# octanis_v1.net
KiCad netlist of a schematic drawn in EAGLE
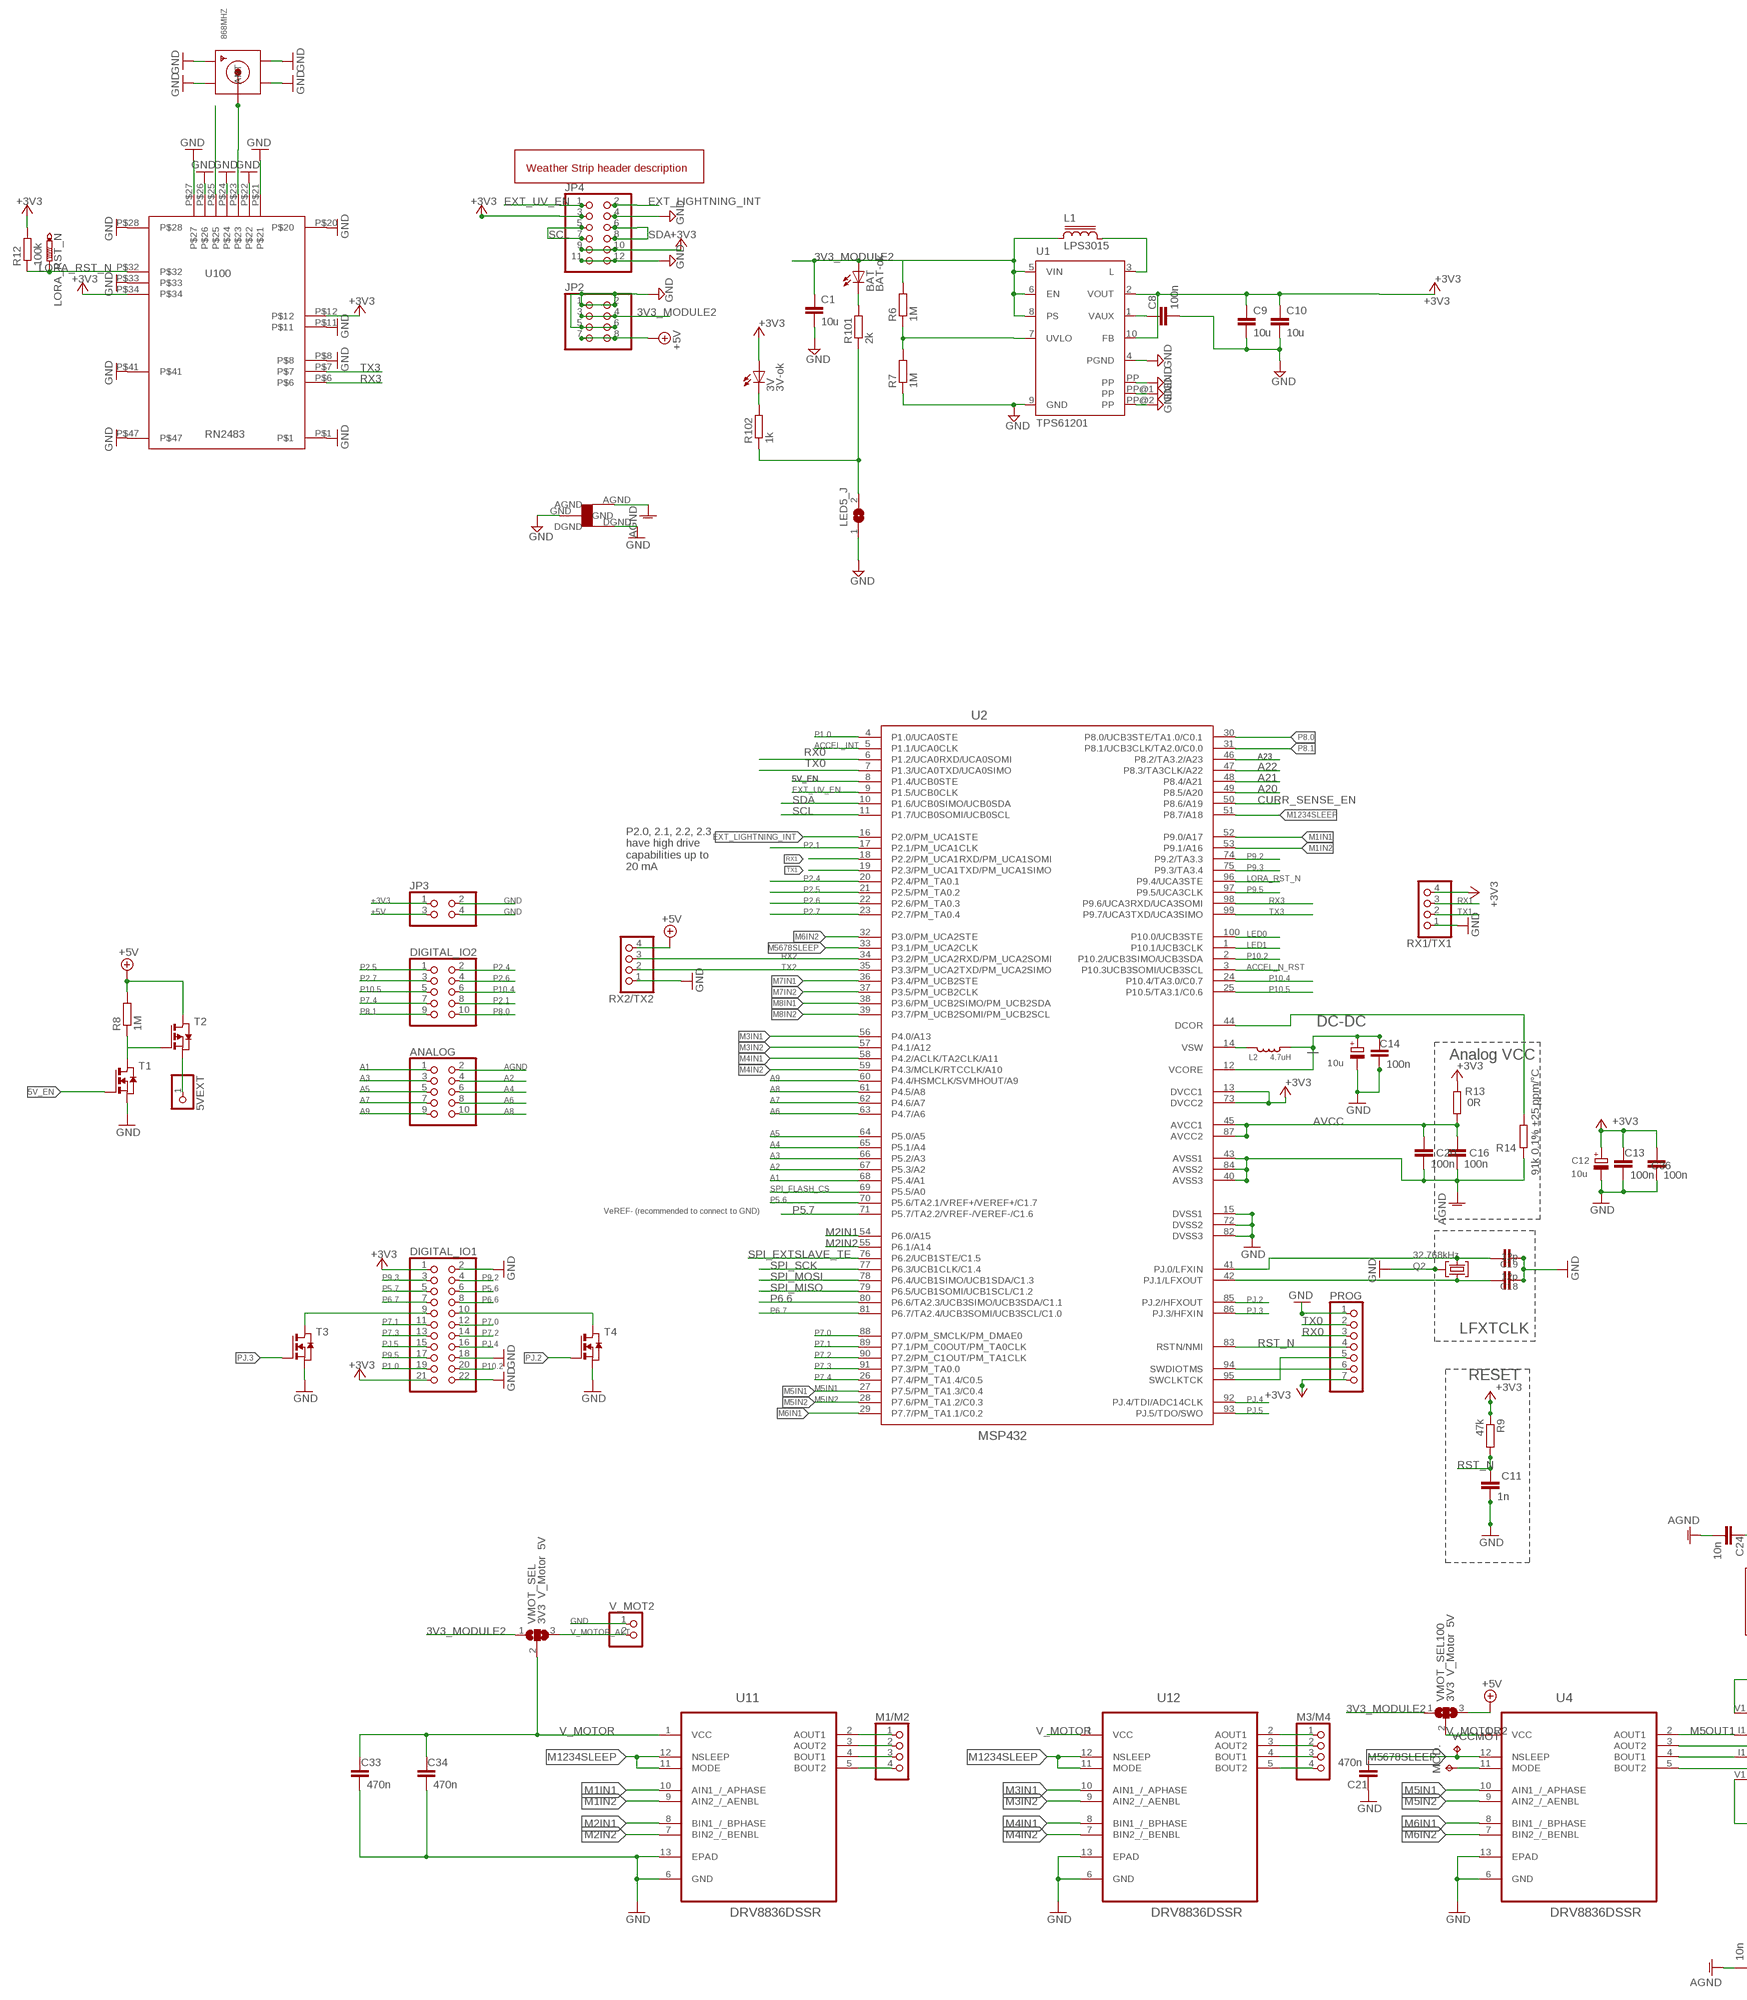
[diagram p0: schematic, sheet 1, part 1 of 2]
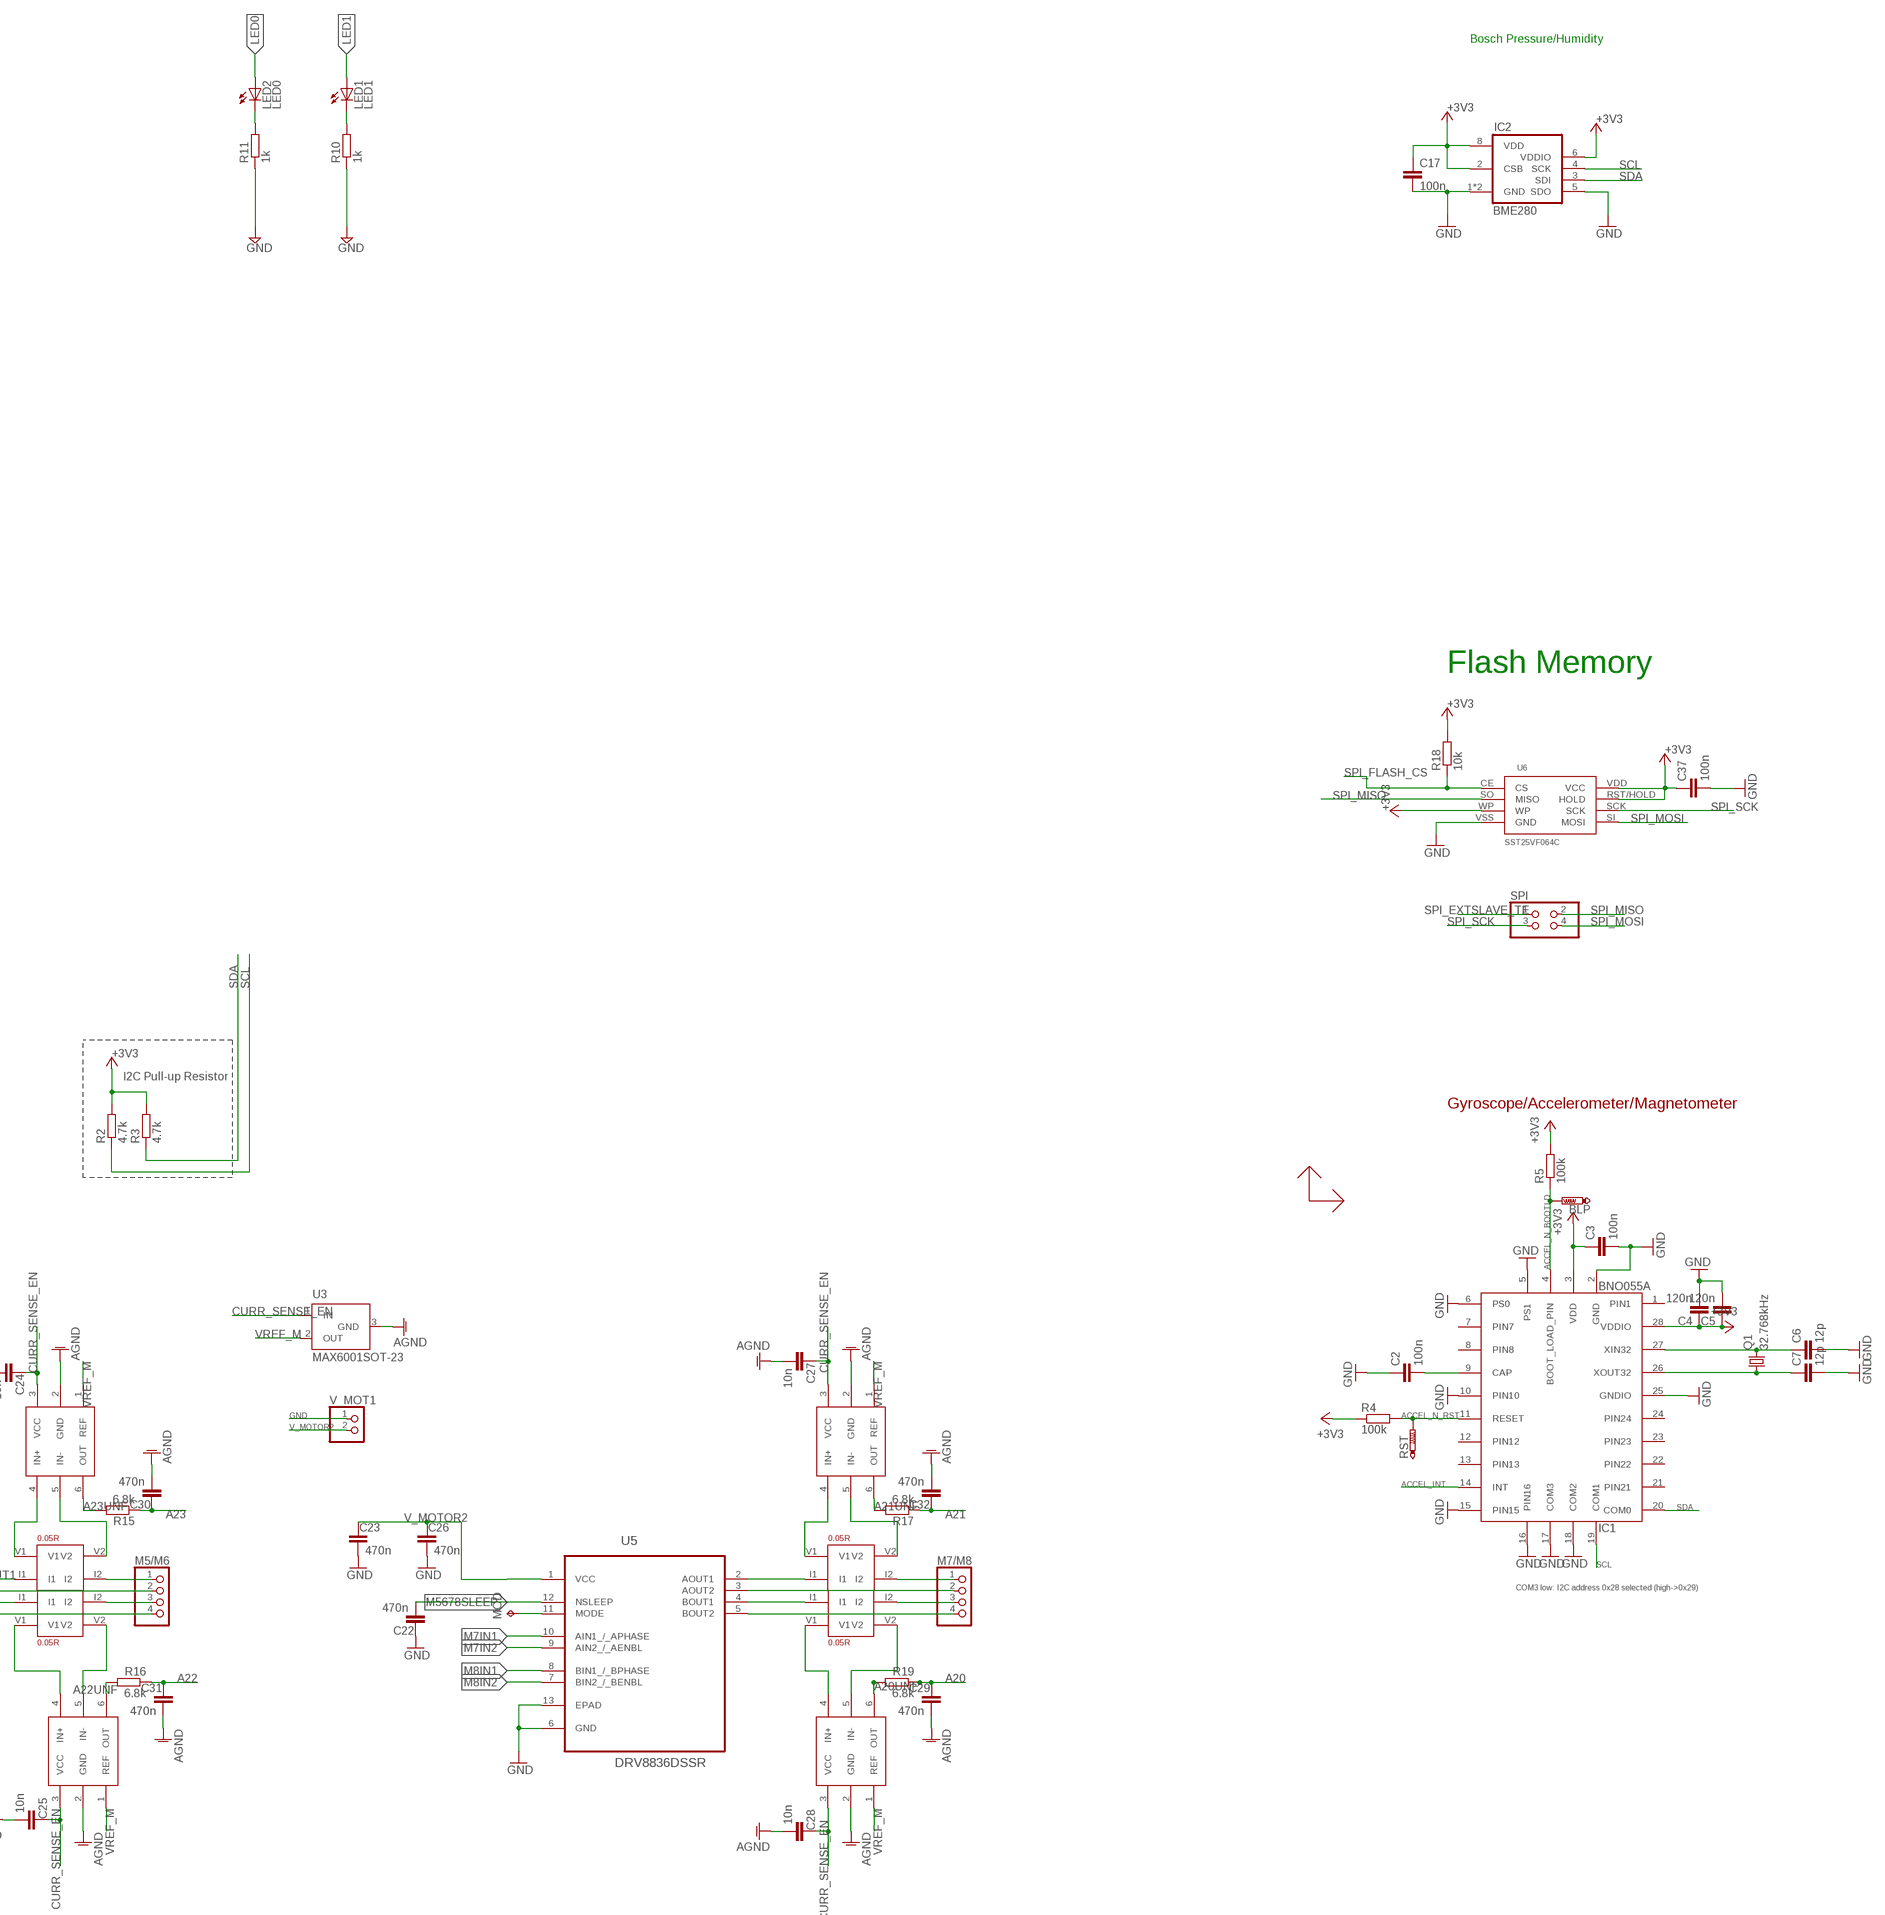
[diagram p1: schematic, sheet 1, part 2 of 2]

(export (version "E")
  (design (tool "Eeschema 10.0.6"))
  (components
    (comp (ref "3V")
      (value "3V-ok")
      (footprint "eagle-import:CHIPLED_0603")
      (libsource (lib "eagle-import") (part "LEDCHIPLED_0603"))
    )
    (comp (ref "5VEXT")
      (value "PINHD-1X1")
      (footprint "eagle-import:1X01")
      (libsource (lib "eagle-import") (part "PINHD-1X1"))
    )
    (comp (ref "868MHZ")
      (value "SMACONNECTOR_EDGE")
      (footprint "eagle-import:SMA_EDGELAUNCH")
      (libsource (lib "eagle-import") (part "SMACONNECTOR_EDGE"))
    )
    (comp (ref "ANALOG")
      (value "PINHD-2X5")
      (footprint "eagle-import:2X05")
      (libsource (lib "eagle-import") (part "PINHD-2X5"))
    )
    (comp (ref "BAT")
      (value "BAT-ok")
      (footprint "eagle-import:CHIPLED_0603")
      (libsource (lib "eagle-import") (part "LEDCHIPLED_0603"))
    )
    (comp (ref "BLP")
      (value "PTR1B1,27")
      (footprint "eagle-import:B1,27")
      (libsource (lib "eagle-import") (part "PTR1B1,27"))
    )
    (comp (ref "C1")
      (value "10u")
      (footprint "eagle-import:C0805K")
      (libsource (lib "eagle-import") (part "C-EUC0805K"))
    )
    (comp (ref "C2")
      (value "100n")
      (footprint "eagle-import:C0603")
      (libsource (lib "eagle-import") (part "C-EUC0603"))
    )
    (comp (ref "C3")
      (value "100n")
      (footprint "eagle-import:C0603")
      (libsource (lib "eagle-import") (part "C-EUC0603"))
    )
    (comp (ref "C4")
      (value "120n")
      (footprint "eagle-import:C0603")
      (libsource (lib "eagle-import") (part "C-EUC0603"))
    )
    (comp (ref "C5")
      (value "120n")
      (footprint "eagle-import:C0603")
      (libsource (lib "eagle-import") (part "C-EUC0603"))
    )
    (comp (ref "C6")
      (value "12p")
      (footprint "eagle-import:C0603")
      (libsource (lib "eagle-import") (part "C-EUC0603"))
    )
    (comp (ref "C7")
      (value "12p")
      (footprint "eagle-import:C0603")
      (libsource (lib "eagle-import") (part "C-EUC0603"))
    )
    (comp (ref "C8")
      (value "100n")
      (footprint "eagle-import:C0603")
      (libsource (lib "eagle-import") (part "C-EUC0603"))
    )
    (comp (ref "C9")
      (value "10u")
      (footprint "eagle-import:C0805K")
      (libsource (lib "eagle-import") (part "C-EUC0805K"))
    )
    (comp (ref "C10")
      (value "10u")
      (footprint "eagle-import:C0805K")
      (libsource (lib "eagle-import") (part "C-EUC0805K"))
    )
    (comp (ref "C11")
      (value "1n")
      (footprint "eagle-import:C0603")
      (libsource (lib "eagle-import") (part "C-EUC0603"))
    )
    (comp (ref "C12")
      (value "10u")
      (footprint "eagle-import:A_3216-18R")
      (libsource (lib "eagle-import") (part "CPOL-EUA/3216-18R"))
    )
    (comp (ref "C13")
      (value "100n")
      (footprint "eagle-import:C0603")
      (libsource (lib "eagle-import") (part "C-EUC0603"))
    )
    (comp (ref "C14")
      (value "100n")
      (footprint "eagle-import:C0603")
      (libsource (lib "eagle-import") (part "C-EUC0603"))
    )
    (comp (ref "C15")
      (value "10u")
      (footprint "eagle-import:A_3216-18R")
      (libsource (lib "eagle-import") (part "CPOL-EUA/3216-18R"))
    )
    (comp (ref "C16")
      (value "100n")
      (footprint "eagle-import:C0402")
      (libsource (lib "eagle-import") (part "C-EUC0402"))
    )
    (comp (ref "C17")
      (value "100n")
      (footprint "eagle-import:C0603")
      (libsource (lib "eagle-import") (part "C-EUC0603"))
    )
    (comp (ref "C18")
      (value "12p")
      (footprint "eagle-import:C0402")
      (libsource (lib "eagle-import") (part "C-EUC0402"))
    )
    (comp (ref "C19")
      (value "12p")
      (footprint "eagle-import:C0402")
      (libsource (lib "eagle-import") (part "C-EUC0402"))
    )
    (comp (ref "C20")
      (value "100n")
      (footprint "eagle-import:C0402")
      (libsource (lib "eagle-import") (part "C-EUC0402"))
    )
    (comp (ref "C21")
      (value "470n")
      (footprint "eagle-import:C0603")
      (libsource (lib "eagle-import") (part "C-EUC0603"))
    )
    (comp (ref "C22")
      (value "470n")
      (footprint "eagle-import:C0603")
      (libsource (lib "eagle-import") (part "C-EUC0603"))
    )
    (comp (ref "C23")
      (value "470n")
      (footprint "eagle-import:C0603")
      (libsource (lib "eagle-import") (part "C-EUC0603"))
    )
    (comp (ref "C24")
      (value "10n")
      (footprint "eagle-import:C0603")
      (libsource (lib "eagle-import") (part "C-EUC0603"))
    )
    (comp (ref "C25")
      (value "10n")
      (footprint "eagle-import:C0603")
      (libsource (lib "eagle-import") (part "C-EUC0603"))
    )
    (comp (ref "C26")
      (value "470n")
      (footprint "eagle-import:C0603")
      (libsource (lib "eagle-import") (part "C-EUC0603"))
    )
    (comp (ref "C27")
      (value "10n")
      (footprint "eagle-import:C0603")
      (libsource (lib "eagle-import") (part "C-EUC0603"))
    )
    (comp (ref "C28")
      (value "10n")
      (footprint "eagle-import:C0603")
      (libsource (lib "eagle-import") (part "C-EUC0603"))
    )
    (comp (ref "C29")
      (value "470n")
      (footprint "eagle-import:C0603")
      (libsource (lib "eagle-import") (part "C-EUC0603"))
    )
    (comp (ref "C30")
      (value "470n")
      (footprint "eagle-import:C0603")
      (libsource (lib "eagle-import") (part "C-EUC0603"))
    )
    (comp (ref "C31")
      (value "470n")
      (footprint "eagle-import:C0603")
      (libsource (lib "eagle-import") (part "C-EUC0603"))
    )
    (comp (ref "C32")
      (value "470n")
      (footprint "eagle-import:C0603")
      (libsource (lib "eagle-import") (part "C-EUC0603"))
    )
    (comp (ref "C33")
      (value "470n")
      (footprint "eagle-import:C0603")
      (libsource (lib "eagle-import") (part "C-EUC0603"))
    )
    (comp (ref "C34")
      (value "470n")
      (footprint "eagle-import:C0603")
      (libsource (lib "eagle-import") (part "C-EUC0603"))
    )
    (comp (ref "C36")
      (value "100n")
      (footprint "eagle-import:C0603")
      (libsource (lib "eagle-import") (part "C-EUC0603"))
    )
    (comp (ref "C37")
      (value "100n")
      (footprint "eagle-import:C0603")
      (libsource (lib "eagle-import") (part "C-EUC0603"))
    )
    (comp (ref "DIGITAL_IO1")
      (value "PINHD-2X11")
      (footprint "eagle-import:2X11")
      (libsource (lib "eagle-import") (part "PINHD-2X11"))
    )
    (comp (ref "DIGITAL_IO2")
      (value "PINHD-2X5")
      (footprint "eagle-import:2X05")
      (libsource (lib "eagle-import") (part "PINHD-2X5"))
    )
    (comp (ref "IC1")
      (value "BNO055A")
      (footprint "eagle-import:BNO055")
      (libsource (lib "eagle-import") (part "BNO055A"))
    )
    (comp (ref "IC2")
      (value "BME280")
      (footprint "eagle-import:BME280")
      (libsource (lib "eagle-import") (part "BME280"))
    )
    (comp (ref "JP2")
      (value "PINHD-2X04_2.54")
      (footprint "eagle-import:2X04")
      (libsource (lib "eagle-import") (part "PINHD-2X04_2.54"))
    )
    (comp (ref "JP3")
      (value "PINHD-2X2")
      (footprint "eagle-import:2X02")
      (libsource (lib "eagle-import") (part "PINHD-2X2"))
    )
    (comp (ref "JP4")
      (value "PINHD-2X06_2.54-SMD")
      (footprint "eagle-import:2X06SMD")
      (libsource (lib "eagle-import") (part "PINHD-2X06_2.54-SMD"))
    )
    (comp (ref "L1")
      (value "LPS3015")
      (footprint "eagle-import:LPS3015")
      (libsource (lib "eagle-import") (part "LPS3015"))
    )
    (comp (ref "L2")
      (value "4.7uH")
      (footprint "eagle-import:0806")
      (libsource (lib "eagle-import") (part "LQM2MP_G0"))
    )
    (comp (ref "LED1")
      (value "LED1")
      (footprint "eagle-import:CHIPLED_0603")
      (libsource (lib "eagle-import") (part "LEDCHIPLED_0603"))
    )
    (comp (ref "LED2")
      (value "LED0")
      (footprint "eagle-import:CHIPLED_0603")
      (libsource (lib "eagle-import") (part "LEDCHIPLED_0603"))
    )
    (comp (ref "LED5_J")
      (value "SJ")
      (footprint "eagle-import:SJ")
      (libsource (lib "eagle-import") (part "SJ"))
    )
    (comp (ref "LORA_RST_N")
      (value "PTR1TP15R")
      (footprint "eagle-import:TP15R")
      (libsource (lib "eagle-import") (part "PTR1TP15R"))
    )
    (comp (ref "M1/M2")
      (value "PINHD-1X04_2.54-S")
      (footprint "eagle-import:1X04-S")
      (libsource (lib "eagle-import") (part "PINHD-1X04_2.54-S"))
    )
    (comp (ref "M3/M4")
      (value "PINHD-1X04_2.54-S")
      (footprint "eagle-import:1X04-S")
      (libsource (lib "eagle-import") (part "PINHD-1X04_2.54-S"))
    )
    (comp (ref "M5/M6")
      (value "PINHD-1X04_2.54-S")
      (footprint "eagle-import:1X04-S")
      (libsource (lib "eagle-import") (part "PINHD-1X04_2.54-S"))
    )
    (comp (ref "M7/M8")
      (value "PINHD-1X04_2.54-S")
      (footprint "eagle-import:1X04-S")
      (libsource (lib "eagle-import") (part "PINHD-1X04_2.54-S"))
    )
    (comp (ref "MOD")
      (value "TPTP06R")
      (footprint "eagle-import:TP06R")
      (libsource (lib "eagle-import") (part "TPTP06R"))
    )
    (comp (ref "MOD.")
      (value "TPTP06R")
      (footprint "eagle-import:TP06R")
      (libsource (lib "eagle-import") (part "TPTP06R"))
    )
    (comp (ref "PROG")
      (value "PINHD-1X72MM_SMD")
      (footprint "eagle-import:1X7SMD")
      (libsource (lib "eagle-import") (part "PINHD-1X72MM_SMD"))
    )
    (comp (ref "Q1")
      (value "32.768kHz")
      (footprint "eagle-import:FC-12M")
      (libsource (lib "eagle-import") (part "FC-12M"))
    )
    (comp (ref "Q2")
      (value "32.768kHz")
      (footprint "eagle-import:MS3V-T1R")
      (libsource (lib "eagle-import") (part "MS3V-T1R"))
    )
    (comp (ref "R2")
      (value "4.7k")
      (footprint "eagle-import:R0603")
      (libsource (lib "eagle-import") (part "R-EU_R0603"))
    )
    (comp (ref "R3")
      (value "4.7k")
      (footprint "eagle-import:R0603")
      (libsource (lib "eagle-import") (part "R-EU_R0603"))
    )
    (comp (ref "R4")
      (value "100k")
      (footprint "eagle-import:R0603")
      (libsource (lib "eagle-import") (part "R-EU_R0603"))
    )
    (comp (ref "R5")
      (value "100k")
      (footprint "eagle-import:R0603")
      (libsource (lib "eagle-import") (part "R-EU_R0603"))
    )
    (comp (ref "R6")
      (value "1M")
      (footprint "eagle-import:R0603")
      (libsource (lib "eagle-import") (part "R-EU_R0603"))
    )
    (comp (ref "R7")
      (value "1M")
      (footprint "eagle-import:R0603")
      (libsource (lib "eagle-import") (part "R-EU_R0603"))
    )
    (comp (ref "R8")
      (value "1M")
      (footprint "eagle-import:R0603")
      (libsource (lib "eagle-import") (part "R-EU_R0603"))
    )
    (comp (ref "R9")
      (value "47k")
      (footprint "eagle-import:R0603")
      (libsource (lib "eagle-import") (part "R-EU_R0603"))
    )
    (comp (ref "R10")
      (value "1k")
      (footprint "eagle-import:R0603")
      (libsource (lib "eagle-import") (part "R-EU_R0603"))
    )
    (comp (ref "R11")
      (value "1k")
      (footprint "eagle-import:R0603")
      (libsource (lib "eagle-import") (part "R-EU_R0603"))
    )
    (comp (ref "R12")
      (value "100k")
      (footprint "eagle-import:R0603")
      (libsource (lib "eagle-import") (part "R-EU_R0603"))
    )
    (comp (ref "R13")
      (value "0R")
      (footprint "eagle-import:R0402")
      (libsource (lib "eagle-import") (part "R-EU_R0402"))
    )
    (comp (ref "R14")
      (value "91k 0.1% ±25 ppm/°C")
      (footprint "eagle-import:R0402")
      (libsource (lib "eagle-import") (part "R-EU_R0402"))
    )
    (comp (ref "R15")
      (value "6.8k")
      (footprint "eagle-import:R0603")
      (libsource (lib "eagle-import") (part "R-EU_R0603"))
    )
    (comp (ref "R16")
      (value "6.8k")
      (footprint "eagle-import:R0603")
      (libsource (lib "eagle-import") (part "R-EU_R0603"))
    )
    (comp (ref "R17")
      (value "6.8k")
      (footprint "eagle-import:R0603")
      (libsource (lib "eagle-import") (part "R-EU_R0603"))
    )
    (comp (ref "R18")
      (value "10k")
      (footprint "eagle-import:R0603")
      (libsource (lib "eagle-import") (part "R-EU_R0603"))
    )
    (comp (ref "R19")
      (value "6.8k")
      (footprint "eagle-import:R0603")
      (libsource (lib "eagle-import") (part "R-EU_R0603"))
    )
    (comp (ref "R101")
      (value "2k")
      (footprint "eagle-import:R0603")
      (libsource (lib "eagle-import") (part "R-EU_R0603"))
    )
    (comp (ref "R102")
      (value "1k")
      (footprint "eagle-import:R0603")
      (libsource (lib "eagle-import") (part "R-EU_R0603"))
    )
    (comp (ref "RS1")
      (value "0.05R")
      (footprint "eagle-import:4PADS_RESISTOR")
      (libsource (lib "eagle-import") (part "CURRENT_RESISTOR"))
    )
    (comp (ref "RS2")
      (value "0.05R")
      (footprint "eagle-import:4PADS_RESISTOR")
      (libsource (lib "eagle-import") (part "CURRENT_RESISTOR"))
    )
    (comp (ref "RS3")
      (value "0.05R")
      (footprint "eagle-import:4PADS_RESISTOR")
      (libsource (lib "eagle-import") (part "CURRENT_RESISTOR"))
    )
    (comp (ref "RS4")
      (value "0.05R")
      (footprint "eagle-import:4PADS_RESISTOR")
      (libsource (lib "eagle-import") (part "CURRENT_RESISTOR"))
    )
    (comp (ref "RST")
      (value "PTR1B1,27")
      (footprint "eagle-import:B1,27")
      (libsource (lib "eagle-import") (part "PTR1B1,27"))
    )
    (comp (ref "RX1/TX1")
      (value "PINHD-1X04_2.54-S")
      (footprint "eagle-import:1X04-S")
      (libsource (lib "eagle-import") (part "PINHD-1X04_2.54-S"))
    )
    (comp (ref "RX2/TX2")
      (value "PINHD-1X04_2.54-S")
      (footprint "eagle-import:1X04-S")
      (libsource (lib "eagle-import") (part "PINHD-1X04_2.54-S"))
    )
    (comp (ref "SPI")
      (value "PINHD-2X2")
      (footprint "eagle-import:2X02")
      (libsource (lib "eagle-import") (part "PINHD-2X2"))
    )
    (comp (ref "T1")
      (value "NMOSSOT23")
      (footprint "eagle-import:SOT-23")
      (libsource (lib "eagle-import") (part "NMOSSOT23"))
    )
    (comp (ref "T2")
      (value "PMOSSOT23")
      (footprint "eagle-import:SOT-23")
      (libsource (lib "eagle-import") (part "PMOSSOT23"))
    )
    (comp (ref "T3")
      (value "NMOSSOT23")
      (footprint "eagle-import:SOT-23")
      (libsource (lib "eagle-import") (part "NMOSSOT23"))
    )
    (comp (ref "T4")
      (value "NMOSSOT23")
      (footprint "eagle-import:SOT-23")
      (libsource (lib "eagle-import") (part "NMOSSOT23"))
    )
    (comp (ref "U$1")
      (value "WEATHER_STRIP_DOCU")
      (footprint "eagle-import:WEATHER_STRIP_DOCU")
      (libsource (lib "eagle-import") (part "WEATHER_STRIP_DOCU"))
    )
    (comp (ref "U$2")
      (value "STARGND")
      (footprint "eagle-import:STAR")
      (libsource (lib "eagle-import") (part "STARGND"))
    )
    (comp (ref "U$3")
      (value "BNO055_COORDINATES")
      (footprint "eagle-import:BNO055_COORDINATES")
      (libsource (lib "eagle-import") (part "BNO055_COORDINATES"))
    )
    (comp (ref "U1")
      (value "TPS61201")
      (footprint "eagle-import:S-PDSO-N10")
      (fields (field (name "MPN") "TPS61201DRCT"))
      (libsource (lib "eagle-import") (part "TPS61201"))
    )
    (comp (ref "U2")
      (value "MSP432")
      (footprint "eagle-import:PZ100")
      (libsource (lib "eagle-import") (part "MSP432"))
    )
    (comp (ref "U3")
      (value "MAX6001SOT-23")
      (footprint "eagle-import:MAX6001")
      (libsource (lib "eagle-import") (part "MAX6001SOT-23"))
    )
    (comp (ref "U4")
      (value "DRV8836DSSR")
      (footprint "eagle-import:SON50P200X300X80-13N")
      (fields (field (name "MPN") "DRV8836DSSR "))
      (libsource (lib "eagle-import") (part "DRV8836DSSR"))
    )
    (comp (ref "U5")
      (value "DRV8836DSSR")
      (footprint "eagle-import:SON50P200X300X80-13N")
      (fields (field (name "MPN") "DRV8836DSSR "))
      (libsource (lib "eagle-import") (part "DRV8836DSSR"))
    )
    (comp (ref "U6")
      (value "SST25VF064C")
      (footprint "eagle-import:SOIC_8-LEAD")
      (libsource (lib "eagle-import") (part "SST25VF064C"))
    )
    (comp (ref "U7")
      (value "INA210")
      (footprint "eagle-import:SC70-6")
      (libsource (lib "eagle-import") (part "INA213"))
    )
    (comp (ref "U8")
      (value "INA210")
      (footprint "eagle-import:SC70-6")
      (libsource (lib "eagle-import") (part "INA213"))
    )
    (comp (ref "U9")
      (value "INA210")
      (footprint "eagle-import:SC70-6")
      (libsource (lib "eagle-import") (part "INA213"))
    )
    (comp (ref "U10")
      (value "INA210")
      (footprint "eagle-import:SC70-6")
      (libsource (lib "eagle-import") (part "INA213"))
    )
    (comp (ref "U11")
      (value "DRV8836DSSR")
      (footprint "eagle-import:SON50P200X300X80-13N")
      (fields (field (name "MPN") "DRV8836DSSR "))
      (libsource (lib "eagle-import") (part "DRV8836DSSR"))
    )
    (comp (ref "U12")
      (value "DRV8836DSSR")
      (footprint "eagle-import:SON50P200X300X80-13N")
      (fields (field (name "MPN") "DRV8836DSSR "))
      (libsource (lib "eagle-import") (part "DRV8836DSSR"))
    )
    (comp (ref "U100")
      (value "RN2483")
      (footprint "eagle-import:RN2483")
      (libsource (lib "eagle-import") (part "RN2483"))
    )
    (comp (ref "VCCMOT")
      (value "TPTP06R")
      (footprint "eagle-import:TP06R")
      (libsource (lib "eagle-import") (part "TPTP06R"))
    )
    (comp (ref "VMOT_SEL")
      (value "3V3 V_Motor 5V")
      (footprint "eagle-import:SJ_2")
      (libsource (lib "eagle-import") (part "SJ2W"))
    )
    (comp (ref "VMOT_SEL100")
      (value "3V3 V_Motor 5V")
      (footprint "eagle-import:SJ_2")
      (libsource (lib "eagle-import") (part "SJ2W"))
    )
    (comp (ref "V_MOT1")
      (value "PINHD-1X02_2.54-S")
      (footprint "eagle-import:1X02-S")
      (libsource (lib "eagle-import") (part "PINHD-1X02_2.54-S"))
    )
    (comp (ref "V_MOT2")
      (value "PINHD-1X02_2.54-S")
      (footprint "eagle-import:1X02-S")
      (libsource (lib "eagle-import") (part "PINHD-1X02_2.54-S"))
    )
  )
  (nets
    (net (code "1") (name "+3V3") (class "Default")
      (node (ref "3V") (pin "A") (pinfunction "A_A") (pintype "passive"))
      (node (ref "C10") (pin "1") (pinfunction "1_1") (pintype "passive"))
      (node (ref "C12") (pin "+") (pinfunction "+_+") (pintype "passive"))
      (node (ref "C13") (pin "2") (pinfunction "2_2") (pintype "passive"))
      (node (ref "C17") (pin "1") (pinfunction "1_1") (pintype "passive"))
      (node (ref "C3") (pin "1") (pinfunction "1_1") (pintype "passive"))
      (node (ref "C36") (pin "2") (pinfunction "2_2") (pintype "passive"))
      (node (ref "C37") (pin "1") (pinfunction "1_1") (pintype "passive"))
      (node (ref "C4") (pin "1") (pinfunction "1_1") (pintype "passive"))
      (node (ref "C5") (pin "1") (pinfunction "1_1") (pintype "passive"))
      (node (ref "C9") (pin "1") (pinfunction "1_1") (pintype "passive"))
      (node (ref "DIGITAL_IO1") (pin "1") (pinfunction "1_1") (pintype "passive"))
      (node (ref "DIGITAL_IO1") (pin "21") (pinfunction "21_21") (pintype "passive"))
      (node (ref "IC1") (pin "28") (pinfunction "VDDIO_28") (pintype "bidirectional"))
      (node (ref "IC1") (pin "3") (pinfunction "VDD_3") (pintype "bidirectional"))
      (node (ref "IC2") (pin "2") (pinfunction "CSB_2") (pintype "input"))
      (node (ref "IC2") (pin "6") (pinfunction "VDDIO_6") (pintype "power_in"))
      (node (ref "IC2") (pin "8") (pinfunction "VDD_8") (pintype "power_in"))
      (node (ref "JP3") (pin "1") (pinfunction "1_1") (pintype "passive"))
      (node (ref "JP4") (pin "10") (pinfunction "10_10") (pintype "passive"))
      (node (ref "JP4") (pin "3") (pinfunction "3_3") (pintype "passive"))
      (node (ref "JP4") (pin "9") (pinfunction "9_9") (pintype "passive"))
      (node (ref "PROG") (pin "7") (pinfunction "7_7") (pintype "passive"))
      (node (ref "R12") (pin "2") (pinfunction "2_2") (pintype "passive"))
      (node (ref "R13") (pin "2") (pinfunction "2_2") (pintype "passive"))
      (node (ref "R18") (pin "2") (pinfunction "2_2") (pintype "passive"))
      (node (ref "R2") (pin "2") (pinfunction "2_2") (pintype "passive"))
      (node (ref "R3") (pin "2") (pinfunction "2_2") (pintype "passive"))
      (node (ref "R4") (pin "1") (pinfunction "1_1") (pintype "passive"))
      (node (ref "R5") (pin "2") (pinfunction "2_2") (pintype "passive"))
      (node (ref "R9") (pin "1") (pinfunction "1_1") (pintype "passive"))
      (node (ref "RX1/TX1") (pin "4") (pinfunction "4_4") (pintype "passive"))
      (node (ref "U1") (pin "10") (pinfunction "FB_10") (pintype "input"))
      (node (ref "U1") (pin "2") (pinfunction "VOUT_2") (pintype "passive"))
      (node (ref "U100") (pin "P$12") (pinfunction "P$12_P$12") (pintype "bidirectional"))
      (node (ref "U100") (pin "P$34") (pinfunction "P$34_P$34") (pintype "bidirectional"))
      (node (ref "U2") (pin "13") (pinfunction "DVCC1_13") (pintype "power_in"))
      (node (ref "U2") (pin "73") (pinfunction "DVCC2_73") (pintype "power_in"))
      (node (ref "U6") (pin "RST/HOLD") (pinfunction "HOLD_RST/HOLD") (pintype "bidirectional"))
      (node (ref "U6") (pin "VDD") (pinfunction "VCC_VDD") (pintype "bidirectional"))
      (node (ref "U6") (pin "WP") (pinfunction "WP_WP") (pintype "bidirectional"))
    )
    (net (code "2") (name "+5V") (class "Default")
      (node (ref "JP2") (pin "7") (pinfunction "7_7") (pintype "passive"))
      (node (ref "JP2") (pin "8") (pinfunction "8_8") (pintype "passive"))
      (node (ref "JP3") (pin "3") (pinfunction "3_3") (pintype "passive"))
      (node (ref "R8") (pin "2") (pinfunction "2_2") (pintype "passive"))
      (node (ref "RX2/TX2") (pin "4") (pinfunction "4_4") (pintype "passive"))
      (node (ref "T2") (pin "1") (pinfunction "D_1") (pintype "passive"))
      (node (ref "VMOT_SEL100") (pin "3") (pinfunction "3_3") (pintype "passive"))
    )
    (net (code "3") (name "/3V3_MODULE2") (class "Default")
      (node (ref "BAT") (pin "A") (pinfunction "A_A") (pintype "passive"))
      (node (ref "C1") (pin "1") (pinfunction "1_1") (pintype "passive"))
      (node (ref "JP2") (pin "3") (pinfunction "3_3") (pintype "passive"))
      (node (ref "JP2") (pin "4") (pinfunction "4_4") (pintype "passive"))
      (node (ref "L1") (pin "1") (pinfunction "1_1") (pintype "passive"))
      (node (ref "R6") (pin "2") (pinfunction "2_2") (pintype "passive"))
      (node (ref "U1") (pin "5") (pinfunction "VIN_5") (pintype "input"))
      (node (ref "U1") (pin "6") (pinfunction "EN_6") (pintype "input"))
      (node (ref "U1") (pin "8") (pinfunction "PS_8") (pintype "input"))
      (node (ref "VMOT_SEL") (pin "1") (pinfunction "1_1") (pintype "passive"))
      (node (ref "VMOT_SEL100") (pin "1") (pinfunction "1_1") (pintype "passive"))
    )
    (net (code "4") (name "/A1") (class "Default")
      (node (ref "ANALOG") (pin "1") (pinfunction "1_1") (pintype "passive"))
      (node (ref "U2") (pin "68") (pinfunction "P5.4/A1_68") (pintype "power_in"))
    )
    (net (code "5") (name "/A2") (class "Default")
      (node (ref "ANALOG") (pin "4") (pinfunction "4_4") (pintype "passive"))
      (node (ref "U2") (pin "67") (pinfunction "P5.3/A2_67") (pintype "power_in"))
    )
    (net (code "6") (name "/A3") (class "Default")
      (node (ref "ANALOG") (pin "3") (pinfunction "3_3") (pintype "passive"))
      (node (ref "U2") (pin "66") (pinfunction "P5.2/A3_66") (pintype "power_in"))
    )
    (net (code "7") (name "/A4") (class "Default")
      (node (ref "ANALOG") (pin "6") (pinfunction "6_6") (pintype "passive"))
      (node (ref "U2") (pin "65") (pinfunction "P5.1/A4_65") (pintype "power_in"))
    )
    (net (code "8") (name "/A5") (class "Default")
      (node (ref "ANALOG") (pin "5") (pinfunction "5_5") (pintype "passive"))
      (node (ref "U2") (pin "64") (pinfunction "P5.0/A5_64") (pintype "power_in"))
    )
    (net (code "9") (name "/A6") (class "Default")
      (node (ref "ANALOG") (pin "8") (pinfunction "8_8") (pintype "passive"))
      (node (ref "U2") (pin "63") (pinfunction "P4.7/A6_63") (pintype "power_in"))
    )
    (net (code "10") (name "/A7") (class "Default")
      (node (ref "ANALOG") (pin "7") (pinfunction "7_7") (pintype "passive"))
      (node (ref "U2") (pin "62") (pinfunction "P4.6/A7_62") (pintype "power_in"))
    )
    (net (code "11") (name "/A8") (class "Default")
      (node (ref "ANALOG") (pin "10") (pinfunction "10_10") (pintype "passive"))
      (node (ref "U2") (pin "61") (pinfunction "P4.5/A8_61") (pintype "power_in"))
    )
    (net (code "12") (name "/A9") (class "Default")
      (node (ref "ANALOG") (pin "9") (pinfunction "9_9") (pintype "passive"))
      (node (ref "U2") (pin "60") (pinfunction "P4.4/HSMCLK/SVMHOUT/A9_60") (pintype "power_in"))
    )
    (net (code "13") (name "/A20") (class "Default")
      (node (ref "C29") (pin "2") (pinfunction "2_2") (pintype "passive"))
      (node (ref "R19") (pin "1") (pinfunction "1_1") (pintype "passive"))
      (node (ref "U2") (pin "49") (pinfunction "P8.5/A20_49") (pintype "power_in"))
    )
    (net (code "14") (name "/A20UNF") (class "Default")
      (node (ref "R19") (pin "2") (pinfunction "2_2") (pintype "passive"))
      (node (ref "U10") (pin "6") (pinfunction "OUT_6") (pintype "bidirectional"))
    )
    (net (code "15") (name "/A21") (class "Default")
      (node (ref "C32") (pin "2") (pinfunction "2_2") (pintype "passive"))
      (node (ref "R17") (pin "1") (pinfunction "1_1") (pintype "passive"))
      (node (ref "U2") (pin "48") (pinfunction "P8.4/A21_48") (pintype "power_in"))
    )
    (net (code "16") (name "/A21UNF") (class "Default")
      (node (ref "R17") (pin "2") (pinfunction "2_2") (pintype "passive"))
      (node (ref "U9") (pin "6") (pinfunction "OUT_6") (pintype "bidirectional"))
    )
    (net (code "17") (name "/A22") (class "Default")
      (node (ref "C31") (pin "2") (pinfunction "2_2") (pintype "passive"))
      (node (ref "R16") (pin "1") (pinfunction "1_1") (pintype "passive"))
      (node (ref "U2") (pin "47") (pinfunction "P8.3/TA3CLK/A22_47") (pintype "power_in"))
    )
    (net (code "18") (name "/A22UNF") (class "Default")
      (node (ref "R16") (pin "2") (pinfunction "2_2") (pintype "passive"))
      (node (ref "U8") (pin "6") (pinfunction "OUT_6") (pintype "bidirectional"))
    )
    (net (code "19") (name "/A23") (class "Default")
      (node (ref "C30") (pin "2") (pinfunction "2_2") (pintype "passive"))
      (node (ref "R15") (pin "1") (pinfunction "1_1") (pintype "passive"))
      (node (ref "U2") (pin "46") (pinfunction "P8.2/TA3.2/A23_46") (pintype "power_in"))
    )
    (net (code "20") (name "/A23UNF") (class "Default")
      (node (ref "R15") (pin "2") (pinfunction "2_2") (pintype "passive"))
      (node (ref "U7") (pin "6") (pinfunction "OUT_6") (pintype "bidirectional"))
    )
    (net (code "21") (name "/ACCEL_INT") (class "Default")
      (node (ref "IC1") (pin "14") (pinfunction "INT_14") (pintype "bidirectional"))
      (node (ref "U2") (pin "5") (pinfunction "P1.1/UCA0CLK_5") (pintype "power_in"))
    )
    (net (code "22") (name "/ACCEL_N_BOOTLD") (class "Default")
      (node (ref "BLP") (pin "TP") (pinfunction "TP_TP") (pintype "input"))
      (node (ref "IC1") (pin "4") (pinfunction "BOOT_LOAD_PIN_4") (pintype "bidirectional"))
      (node (ref "R5") (pin "1") (pinfunction "1_1") (pintype "passive"))
    )
    (net (code "23") (name "/ACCEL_N_RST") (class "Default")
      (node (ref "IC1") (pin "11") (pinfunction "RESET_11") (pintype "bidirectional"))
      (node (ref "R4") (pin "2") (pinfunction "2_2") (pintype "passive"))
      (node (ref "RST") (pin "TP") (pinfunction "TP_TP") (pintype "input"))
      (node (ref "U2") (pin "3") (pinfunction "P10.3UCB3SOMI/UCB3SCL_3") (pintype "power_in"))
    )
    (net (code "24") (name "/AVCC") (class "Default")
      (node (ref "C16") (pin "1") (pinfunction "1_1") (pintype "passive"))
      (node (ref "C20") (pin "1") (pinfunction "1_1") (pintype "passive"))
      (node (ref "R13") (pin "1") (pinfunction "1_1") (pintype "passive"))
      (node (ref "U2") (pin "45") (pinfunction "AVCC1_45") (pintype "power_in"))
      (node (ref "U2") (pin "87") (pinfunction "AVCC2_87") (pintype "power_in"))
    )
    (net (code "25") (name "/CURR_SENSE_EN") (class "Default")
      (node (ref "C24") (pin "2") (pinfunction "2_2") (pintype "passive"))
      (node (ref "C25") (pin "2") (pinfunction "2_2") (pintype "passive"))
      (node (ref "C27") (pin "2") (pinfunction "2_2") (pintype "passive"))
      (node (ref "C28") (pin "2") (pinfunction "2_2") (pintype "passive"))
      (node (ref "U10") (pin "3") (pinfunction "VCC_3") (pintype "bidirectional"))
      (node (ref "U2") (pin "50") (pinfunction "P8.6/A19_50") (pintype "power_in"))
      (node (ref "U3") (pin "1") (pinfunction "IN_1") (pintype "input"))
      (node (ref "U7") (pin "3") (pinfunction "VCC_3") (pintype "bidirectional"))
      (node (ref "U8") (pin "3") (pinfunction "VCC_3") (pintype "bidirectional"))
      (node (ref "U9") (pin "3") (pinfunction "VCC_3") (pintype "bidirectional"))
    )
    (net (code "26") (name "/EXT_UV_EN") (class "Default")
      (node (ref "JP4") (pin "1") (pinfunction "1_1") (pintype "passive"))
      (node (ref "U2") (pin "9") (pinfunction "P1.5/UCB0CLK_9") (pintype "power_in"))
    )
    (net (code "27") (name "/LORA_RST_N") (class "Default")
      (node (ref "LORA_RST_N") (pin "TP") (pinfunction "TP_TP") (pintype "input"))
      (node (ref "R12") (pin "1") (pinfunction "1_1") (pintype "passive"))
      (node (ref "U100") (pin "P$32") (pinfunction "P$32_P$32") (pintype "bidirectional"))
      (node (ref "U2") (pin "96") (pinfunction "P9.4/UCA3STE_96") (pintype "power_in"))
    )
    (net (code "28") (name "/M5OUT1") (class "Default")
      (node (ref "RS1") (pin "I1") (pinfunction "I1_I1") (pintype "bidirectional"))
      (node (ref "U4") (pin "2") (pinfunction "AOUT1_2") (pintype "output"))
    )
    (net (code "29") (name "/P1.0") (class "Default")
      (node (ref "DIGITAL_IO1") (pin "19") (pinfunction "19_19") (pintype "passive"))
      (node (ref "U2") (pin "4") (pinfunction "P1.0/UCA0STE_4") (pintype "power_in"))
    )
    (net (code "30") (name "/P2.1") (class "Default")
      (node (ref "DIGITAL_IO2") (pin "8") (pinfunction "8_8") (pintype "passive"))
      (node (ref "U2") (pin "17") (pinfunction "P2.1/PM_UCA1CLK_17") (pintype "power_in"))
    )
    (net (code "31") (name "/P2.4") (class "Default")
      (node (ref "DIGITAL_IO2") (pin "2") (pinfunction "2_2") (pintype "passive"))
      (node (ref "U2") (pin "20") (pinfunction "P2.4/PM_TA0.1_20") (pintype "power_in"))
    )
    (net (code "32") (name "/P2.5") (class "Default")
      (node (ref "DIGITAL_IO2") (pin "1") (pinfunction "1_1") (pintype "passive"))
      (node (ref "U2") (pin "21") (pinfunction "P2.5/PM_TA0.2_21") (pintype "power_in"))
    )
    (net (code "33") (name "/P2.6") (class "Default")
      (node (ref "DIGITAL_IO2") (pin "4") (pinfunction "4_4") (pintype "passive"))
      (node (ref "U2") (pin "22") (pinfunction "P2.6/PM_TA0.3_22") (pintype "power_in"))
    )
    (net (code "34") (name "/P2.7") (class "Default")
      (node (ref "DIGITAL_IO2") (pin "3") (pinfunction "3_3") (pintype "passive"))
      (node (ref "U2") (pin "23") (pinfunction "P2.7/PM_TA0.4_23") (pintype "power_in"))
    )
    (net (code "35") (name "/P5.6") (class "Default")
      (node (ref "DIGITAL_IO1") (pin "6") (pinfunction "6_6") (pintype "passive"))
      (node (ref "U2") (pin "70") (pinfunction "P5.6/TA2.1/VREF+/VEREF+/C1.7_70") (pintype "power_in"))
    )
    (net (code "36") (name "/P5.7") (class "Default")
      (node (ref "DIGITAL_IO1") (pin "5") (pinfunction "5_5") (pintype "passive"))
      (node (ref "U2") (pin "71") (pinfunction "P5.7/TA2.2/VREF-/VEREF-/C1.6_71") (pintype "power_in"))
    )
    (net (code "37") (name "/P6.6") (class "Default")
      (node (ref "DIGITAL_IO1") (pin "8") (pinfunction "8_8") (pintype "passive"))
      (node (ref "U2") (pin "80") (pinfunction "P6.6/TA2.3/UCB3SIMO/UCB3SDA/C1.1_80") (pintype "power_in"))
    )
    (net (code "38") (name "/P6.7") (class "Default")
      (node (ref "DIGITAL_IO1") (pin "7") (pinfunction "7_7") (pintype "passive"))
      (node (ref "U2") (pin "81") (pinfunction "P6.7/TA2.4/UCB3SOMI/UCB3SCL/C1.0_81") (pintype "power_in"))
    )
    (net (code "39") (name "/P7.0") (class "Default")
      (node (ref "DIGITAL_IO1") (pin "12") (pinfunction "12_12") (pintype "passive"))
      (node (ref "U2") (pin "88") (pinfunction "P7.0/PM_SMCLK/PM_DMAE0_88") (pintype "power_in"))
    )
    (net (code "40") (name "/P7.1") (class "Default")
      (node (ref "DIGITAL_IO1") (pin "11") (pinfunction "11_11") (pintype "passive"))
      (node (ref "U2") (pin "89") (pinfunction "P7.1/PM_C0OUT/PM_TA0CLK_89") (pintype "power_in"))
    )
    (net (code "41") (name "/P7.2") (class "Default")
      (node (ref "DIGITAL_IO1") (pin "14") (pinfunction "14_14") (pintype "passive"))
      (node (ref "U2") (pin "90") (pinfunction "P7.2/PM_C1OUT/PM_TA1CLK_90") (pintype "power_in"))
    )
    (net (code "42") (name "/P7.3") (class "Default")
      (node (ref "DIGITAL_IO1") (pin "13") (pinfunction "13_13") (pintype "passive"))
      (node (ref "U2") (pin "91") (pinfunction "P7.3/PM_TA0.0_91") (pintype "power_in"))
    )
    (net (code "43") (name "/P7.4") (class "Default")
      (node (ref "DIGITAL_IO2") (pin "7") (pinfunction "7_7") (pintype "passive"))
      (node (ref "U2") (pin "26") (pinfunction "P7.4/PM_TA1.4/C0.5_26") (pintype "power_in"))
    )
    (net (code "44") (name "/P9.2") (class "Default")
      (node (ref "DIGITAL_IO1") (pin "4") (pinfunction "4_4") (pintype "passive"))
      (node (ref "U2") (pin "74") (pinfunction "P9.2/TA3.3_74") (pintype "power_in"))
    )
    (net (code "45") (name "/P9.3") (class "Default")
      (node (ref "DIGITAL_IO1") (pin "3") (pinfunction "3_3") (pintype "passive"))
      (node (ref "U2") (pin "75") (pinfunction "P9.3/TA3.4_75") (pintype "power_in"))
    )
    (net (code "46") (name "/P9.5") (class "Default")
      (node (ref "DIGITAL_IO1") (pin "17") (pinfunction "17_17") (pintype "passive"))
      (node (ref "U2") (pin "97") (pinfunction "P9.5/UCA3CLK_97") (pintype "power_in"))
    )
    (net (code "47") (name "/P10.2") (class "Default")
      (node (ref "DIGITAL_IO1") (pin "20") (pinfunction "20_20") (pintype "passive"))
      (node (ref "U2") (pin "2") (pinfunction "P10.2/UCB3SIMO/UCB3SDA_2") (pintype "power_in"))
    )
    (net (code "48") (name "/P10.4") (class "Default")
      (node (ref "DIGITAL_IO2") (pin "6") (pinfunction "6_6") (pintype "passive"))
      (node (ref "U2") (pin "24") (pinfunction "P10.4/TA3.0/C0.7_24") (pintype "power_in"))
    )
    (net (code "49") (name "/P10.5") (class "Default")
      (node (ref "DIGITAL_IO2") (pin "5") (pinfunction "5_5") (pintype "passive"))
      (node (ref "U2") (pin "25") (pinfunction "P10.5/TA3.1/C0.6_25") (pintype "power_in"))
    )
    (net (code "50") (name "/PJ.4") (class "Default")
      (node (ref "DIGITAL_IO1") (pin "16") (pinfunction "16_16") (pintype "passive"))
      (node (ref "U2") (pin "92") (pinfunction "PJ.4/TDI/ADC14CLK_92") (pintype "power_in"))
    )
    (net (code "51") (name "/PJ.5") (class "Default")
      (node (ref "DIGITAL_IO1") (pin "15") (pinfunction "15_15") (pintype "passive"))
      (node (ref "U2") (pin "93") (pinfunction "PJ.5/TDO/SWO_93") (pintype "power_in"))
    )
    (net (code "52") (name "/RST_N") (class "Default")
      (node (ref "C11") (pin "2") (pinfunction "2_2") (pintype "passive"))
      (node (ref "PROG") (pin "4") (pinfunction "4_4") (pintype "passive"))
      (node (ref "R9") (pin "2") (pinfunction "2_2") (pintype "passive"))
      (node (ref "U2") (pin "83") (pinfunction "RSTN/NMI_83") (pintype "power_in"))
    )
    (net (code "53") (name "/RX0") (class "Default")
      (node (ref "PROG") (pin "3") (pinfunction "3_3") (pintype "passive"))
      (node (ref "U2") (pin "6") (pinfunction "P1.2/UCA0RXD/UCA0SOMI_6") (pintype "power_in"))
    )
    (net (code "54") (name "/RX2") (class "Default")
      (node (ref "RX2/TX2") (pin "3") (pinfunction "3_3") (pintype "passive"))
      (node (ref "U2") (pin "34") (pinfunction "P3.2/PM_UCA2RXD/PM_UCA2SOMI_34") (pintype "power_in"))
    )
    (net (code "55") (name "/RX3") (class "Default")
      (node (ref "U100") (pin "P$6") (pinfunction "P$6_P$6") (pintype "bidirectional"))
      (node (ref "U2") (pin "98") (pinfunction "P9.6/UCA3RXD/UCA3SOMI_98") (pintype "power_in"))
    )
    (net (code "56") (name "/SCL") (class "Default")
      (node (ref "IC1") (pin "19") (pinfunction "COM1_19") (pintype "bidirectional"))
      (node (ref "IC2") (pin "4") (pinfunction "SCK_4") (pintype "bidirectional"))
      (node (ref "JP4") (pin "5") (pinfunction "5_5") (pintype "passive"))
      (node (ref "JP4") (pin "7") (pinfunction "7_7") (pintype "passive"))
      (node (ref "R2") (pin "1") (pinfunction "1_1") (pintype "passive"))
      (node (ref "U2") (pin "11") (pinfunction "P1.7/UCB0SOMI/UCB0SCL_11") (pintype "power_in"))
    )
    (net (code "57") (name "/SDA") (class "Default")
      (node (ref "IC1") (pin "20") (pinfunction "COM0_20") (pintype "bidirectional"))
      (node (ref "IC2") (pin "3") (pinfunction "SDI_3") (pintype "bidirectional"))
      (node (ref "JP4") (pin "6") (pinfunction "6_6") (pintype "passive"))
      (node (ref "JP4") (pin "8") (pinfunction "8_8") (pintype "passive"))
      (node (ref "R3") (pin "1") (pinfunction "1_1") (pintype "passive"))
      (node (ref "U2") (pin "10") (pinfunction "P1.6/UCB0SIMO/UCB0SDA_10") (pintype "power_in"))
    )
    (net (code "58") (name "/SPI_EXTSLAVE_TE") (class "Default")
      (node (ref "SPI") (pin "1") (pinfunction "1_1") (pintype "passive"))
      (node (ref "U2") (pin "76") (pinfunction "P6.2/UCB1STE/C1.5_76") (pintype "power_in"))
    )
    (net (code "59") (name "/SPI_FLASH_CS") (class "Default")
      (node (ref "R18") (pin "1") (pinfunction "1_1") (pintype "passive"))
      (node (ref "U2") (pin "69") (pinfunction "P5.5/A0_69") (pintype "power_in"))
      (node (ref "U6") (pin "CE") (pinfunction "CS_CE") (pintype "bidirectional"))
    )
    (net (code "60") (name "/SPI_MISO") (class "Default")
      (node (ref "SPI") (pin "2") (pinfunction "2_2") (pintype "passive"))
      (node (ref "U2") (pin "79") (pinfunction "P6.5/UCB1SOMI/UCB1SCL/C1.2_79") (pintype "power_in"))
      (node (ref "U6") (pin "SO") (pinfunction "MISO_SO") (pintype "bidirectional"))
    )
    (net (code "61") (name "/SPI_MOSI") (class "Default")
      (node (ref "SPI") (pin "4") (pinfunction "4_4") (pintype "passive"))
      (node (ref "U2") (pin "78") (pinfunction "P6.4/UCB1SIMO/UCB1SDA/C1.3_78") (pintype "power_in"))
      (node (ref "U6") (pin "SI") (pinfunction "MOSI_SI") (pintype "bidirectional"))
    )
    (net (code "62") (name "/SPI_SCK") (class "Default")
      (node (ref "SPI") (pin "3") (pinfunction "3_3") (pintype "passive"))
      (node (ref "U2") (pin "77") (pinfunction "P6.3/UCB1CLK/C1.4_77") (pintype "power_in"))
      (node (ref "U6") (pin "SCK") (pinfunction "SCK_SCK") (pintype "bidirectional"))
    )
    (net (code "63") (name "/TX0") (class "Default")
      (node (ref "PROG") (pin "2") (pinfunction "2_2") (pintype "passive"))
      (node (ref "U2") (pin "7") (pinfunction "P1.3/UCA0TXD/UCA0SIMO_7") (pintype "power_in"))
    )
    (net (code "64") (name "/TX2") (class "Default")
      (node (ref "RX2/TX2") (pin "2") (pinfunction "2_2") (pintype "passive"))
      (node (ref "U2") (pin "35") (pinfunction "P3.3/PM_UCA2TXD/PM_UCA2SIMO_35") (pintype "power_in"))
    )
    (net (code "65") (name "/TX3") (class "Default")
      (node (ref "U100") (pin "P$7") (pinfunction "P$7_P$7") (pintype "bidirectional"))
      (node (ref "U2") (pin "99") (pinfunction "P9.7/UCA3TXD/UCA3SIMO_99") (pintype "power_in"))
    )
    (net (code "66") (name "/VREF_M") (class "Default")
      (node (ref "U10") (pin "1") (pinfunction "REF_1") (pintype "bidirectional"))
      (node (ref "U3") (pin "2") (pinfunction "OUT_2") (pintype "output"))
      (node (ref "U7") (pin "1") (pinfunction "REF_1") (pintype "bidirectional"))
      (node (ref "U8") (pin "1") (pinfunction "REF_1") (pintype "bidirectional"))
      (node (ref "U9") (pin "1") (pinfunction "REF_1") (pintype "bidirectional"))
    )
    (net (code "67") (name "/V_MOTOR") (class "Default")
      (node (ref "C33") (pin "2") (pinfunction "2_2") (pintype "passive"))
      (node (ref "C34") (pin "2") (pinfunction "2_2") (pintype "passive"))
      (node (ref "U11") (pin "1") (pinfunction "VCC_1") (pintype "power_in"))
      (node (ref "U12") (pin "1") (pinfunction "VCC_1") (pintype "power_in"))
      (node (ref "VMOT_SEL") (pin "2") (pinfunction "2_2") (pintype "passive"))
    )
    (net (code "68") (name "/V_MOTOR2") (class "Default")
      (node (ref "C23") (pin "2") (pinfunction "2_2") (pintype "passive"))
      (node (ref "C26") (pin "2") (pinfunction "2_2") (pintype "passive"))
      (node (ref "U4") (pin "1") (pinfunction "VCC_1") (pintype "power_in"))
      (node (ref "U5") (pin "1") (pinfunction "VCC_1") (pintype "power_in"))
      (node (ref "VMOT_SEL100") (pin "2") (pinfunction "2_2") (pintype "passive"))
      (node (ref "V_MOT1") (pin "2") (pinfunction "2_2") (pintype "passive"))
    )
    (net (code "69") (name "/V_MOTOR_ALT") (class "Default")
      (node (ref "VMOT_SEL") (pin "3") (pinfunction "3_3") (pintype "passive"))
      (node (ref "V_MOT2") (pin "2") (pinfunction "2_2") (pintype "passive"))
    )
    (net (code "70") (name "5V_EN") (class "Default")
      (node (ref "T1") (pin "3") (pinfunction "G_3") (pintype "passive"))
      (node (ref "U2") (pin "8") (pinfunction "P1.4/UCB0STE_8") (pintype "power_in"))
    )
    (net (code "71") (name "AGND") (class "Default")
      (node (ref "ANALOG") (pin "2") (pinfunction "2_2") (pintype "passive"))
      (node (ref "C16") (pin "2") (pinfunction "2_2") (pintype "passive"))
      (node (ref "C20") (pin "2") (pinfunction "2_2") (pintype "passive"))
      (node (ref "C24") (pin "1") (pinfunction "1_1") (pintype "passive"))
      (node (ref "C25") (pin "1") (pinfunction "1_1") (pintype "passive"))
      (node (ref "C27") (pin "1") (pinfunction "1_1") (pintype "passive"))
      (node (ref "C28") (pin "1") (pinfunction "1_1") (pintype "passive"))
      (node (ref "C29") (pin "1") (pinfunction "1_1") (pintype "passive"))
      (node (ref "C30") (pin "1") (pinfunction "1_1") (pintype "passive"))
      (node (ref "C31") (pin "1") (pinfunction "1_1") (pintype "passive"))
      (node (ref "C32") (pin "1") (pinfunction "1_1") (pintype "passive"))
      (node (ref "R14") (pin "2") (pinfunction "2_2") (pintype "passive"))
      (node (ref "U$2") (pin "AGND") (pinfunction "AGND_AGND") (pintype "output"))
      (node (ref "U10") (pin "2") (pinfunction "GND_2") (pintype "bidirectional"))
      (node (ref "U2") (pin "40") (pinfunction "AVSS3_40") (pintype "power_in"))
      (node (ref "U2") (pin "43") (pinfunction "AVSS1_43") (pintype "power_in"))
      (node (ref "U2") (pin "84") (pinfunction "AVSS2_84") (pintype "power_in"))
      (node (ref "U3") (pin "3") (pinfunction "GND_3") (pintype "power_in"))
      (node (ref "U7") (pin "2") (pinfunction "GND_2") (pintype "bidirectional"))
      (node (ref "U8") (pin "2") (pinfunction "GND_2") (pintype "bidirectional"))
      (node (ref "U9") (pin "2") (pinfunction "GND_2") (pintype "bidirectional"))
    )
    (net (code "72") (name "EXT_LIGHTNING_INT") (class "Default")
      (node (ref "JP4") (pin "2") (pinfunction "2_2") (pintype "passive"))
      (node (ref "U2") (pin "16") (pinfunction "P2.0/PM_UCA1STE_16") (pintype "power_in"))
    )
    (net (code "73") (name "GND") (class "Default")
      (node (ref "868MHZ") (pin "GND@1") (pinfunction "GND4_GND@1") (pintype "power_in"))
      (node (ref "868MHZ") (pin "GND@2") (pinfunction "GND3_GND@2") (pintype "power_in"))
      (node (ref "868MHZ") (pin "GND@3") (pinfunction "GND2_GND@3") (pintype "power_in"))
      (node (ref "868MHZ") (pin "GND@4") (pinfunction "GND1_GND@4") (pintype "power_in"))
      (node (ref "C1") (pin "2") (pinfunction "2_2") (pintype "passive"))
      (node (ref "C10") (pin "2") (pinfunction "2_2") (pintype "passive"))
      (node (ref "C11") (pin "1") (pinfunction "1_1") (pintype "passive"))
      (node (ref "C12") (pin "-") (pinfunction "-_-") (pintype "passive"))
      (node (ref "C13") (pin "1") (pinfunction "1_1") (pintype "passive"))
      (node (ref "C14") (pin "1") (pinfunction "1_1") (pintype "passive"))
      (node (ref "C15") (pin "-") (pinfunction "-_-") (pintype "passive"))
      (node (ref "C17") (pin "2") (pinfunction "2_2") (pintype "passive"))
      (node (ref "C18") (pin "1") (pinfunction "1_1") (pintype "passive"))
      (node (ref "C19") (pin "1") (pinfunction "1_1") (pintype "passive"))
      (node (ref "C2") (pin "1") (pinfunction "1_1") (pintype "passive"))
      (node (ref "C21") (pin "2") (pinfunction "2_2") (pintype "passive"))
      (node (ref "C22") (pin "2") (pinfunction "2_2") (pintype "passive"))
      (node (ref "C23") (pin "1") (pinfunction "1_1") (pintype "passive"))
      (node (ref "C26") (pin "1") (pinfunction "1_1") (pintype "passive"))
      (node (ref "C3") (pin "2") (pinfunction "2_2") (pintype "passive"))
      (node (ref "C33") (pin "1") (pinfunction "1_1") (pintype "passive"))
      (node (ref "C34") (pin "1") (pinfunction "1_1") (pintype "passive"))
      (node (ref "C36") (pin "1") (pinfunction "1_1") (pintype "passive"))
      (node (ref "C37") (pin "2") (pinfunction "2_2") (pintype "passive"))
      (node (ref "C4") (pin "2") (pinfunction "2_2") (pintype "passive"))
      (node (ref "C5") (pin "2") (pinfunction "2_2") (pintype "passive"))
      (node (ref "C6") (pin "2") (pinfunction "2_2") (pintype "passive"))
      (node (ref "C7") (pin "2") (pinfunction "2_2") (pintype "passive"))
      (node (ref "C8") (pin "2") (pinfunction "2_2") (pintype "passive"))
      (node (ref "C9") (pin "2") (pinfunction "2_2") (pintype "passive"))
      (node (ref "DIGITAL_IO1") (pin "18") (pinfunction "18_18") (pintype "passive"))
      (node (ref "DIGITAL_IO1") (pin "2") (pinfunction "2_2") (pintype "passive"))
      (node (ref "DIGITAL_IO1") (pin "22") (pinfunction "22_22") (pintype "passive"))
      (node (ref "IC1") (pin "10") (pinfunction "PIN10_10") (pintype "bidirectional"))
      (node (ref "IC1") (pin "15") (pinfunction "PIN15_15") (pintype "bidirectional"))
      (node (ref "IC1") (pin "16") (pinfunction "PIN16_16") (pintype "bidirectional"))
      (node (ref "IC1") (pin "17") (pinfunction "COM3_17") (pintype "bidirectional"))
      (node (ref "IC1") (pin "18") (pinfunction "COM2_18") (pintype "bidirectional"))
      (node (ref "IC1") (pin "2") (pinfunction "GND_2") (pintype "bidirectional"))
      (node (ref "IC1") (pin "25") (pinfunction "GNDIO_25") (pintype "bidirectional"))
      (node (ref "IC1") (pin "5") (pinfunction "PS1_5") (pintype "bidirectional"))
      (node (ref "IC1") (pin "6") (pinfunction "PS0_6") (pintype "bidirectional"))
      (node (ref "IC2") (pin "1") (pinfunction "GND_1") (pintype "power_in"))
      (node (ref "IC2") (pin "5") (pinfunction "SDO_5") (pintype "input"))
      (node (ref "IC2") (pin "7") (pinfunction "GND_7") (pintype "power_in"))
      (node (ref "JP2") (pin "1") (pinfunction "1_1") (pintype "passive"))
      (node (ref "JP2") (pin "2") (pinfunction "2_2") (pintype "passive"))
      (node (ref "JP2") (pin "5") (pinfunction "5_5") (pintype "passive"))
      (node (ref "JP2") (pin "6") (pinfunction "6_6") (pintype "passive"))
      (node (ref "JP3") (pin "2") (pinfunction "2_2") (pintype "passive"))
      (node (ref "JP3") (pin "4") (pinfunction "4_4") (pintype "passive"))
      (node (ref "JP4") (pin "11") (pinfunction "11_11") (pintype "passive"))
      (node (ref "JP4") (pin "12") (pinfunction "12_12") (pintype "passive"))
      (node (ref "JP4") (pin "4") (pinfunction "4_4") (pintype "passive"))
      (node (ref "LED5_J") (pin "1") (pinfunction "1_1") (pintype "passive"))
      (node (ref "PROG") (pin "1") (pinfunction "1_1") (pintype "passive"))
      (node (ref "Q2") (pin "P3") (pinfunction "GND_P3") (pintype "power_in"))
      (node (ref "R10") (pin "1") (pinfunction "1_1") (pintype "passive"))
      (node (ref "R11") (pin "1") (pinfunction "1_1") (pintype "passive"))
      (node (ref "R7") (pin "1") (pinfunction "1_1") (pintype "passive"))
      (node (ref "RX1/TX1") (pin "1") (pinfunction "1_1") (pintype "passive"))
      (node (ref "RX2/TX2") (pin "1") (pinfunction "1_1") (pintype "passive"))
      (node (ref "T1") (pin "2") (pinfunction "S_2") (pintype "passive"))
      (node (ref "T3") (pin "2") (pinfunction "S_2") (pintype "passive"))
      (node (ref "T4") (pin "2") (pinfunction "S_2") (pintype "passive"))
      (node (ref "U$2") (pin "DGND") (pinfunction "DGND_DGND") (pintype "output"))
      (node (ref "U$2") (pin "GND") (pinfunction "GND_GND") (pintype "power_in"))
      (node (ref "U1") (pin "4") (pinfunction "PGND_4") (pintype "power_in"))
      (node (ref "U1") (pin "9") (pinfunction "GND_9") (pintype "power_in"))
      (node (ref "U1") (pin "PP") (pinfunction "PP_PP") (pintype "power_in"))
      (node (ref "U1") (pin "PP@1") (pinfunction "PP_PP@1") (pintype "power_in"))
      (node (ref "U1") (pin "PP@2") (pinfunction "PP_PP@2") (pintype "power_in"))
      (node (ref "U100") (pin "P$1") (pinfunction "P$1_P$1") (pintype "bidirectional"))
      (node (ref "U100") (pin "P$11") (pinfunction "P$11_P$11") (pintype "bidirectional"))
      (node (ref "U100") (pin "P$20") (pinfunction "P$20_P$20") (pintype "bidirectional"))
      (node (ref "U100") (pin "P$21") (pinfunction "P$21_P$21") (pintype "bidirectional"))
      (node (ref "U100") (pin "P$22") (pinfunction "P$22_P$22") (pintype "bidirectional"))
      (node (ref "U100") (pin "P$24") (pinfunction "P$24_P$24") (pintype "bidirectional"))
      (node (ref "U100") (pin "P$26") (pinfunction "P$26_P$26") (pintype "bidirectional"))
      (node (ref "U100") (pin "P$27") (pinfunction "P$27_P$27") (pintype "bidirectional"))
      (node (ref "U100") (pin "P$28") (pinfunction "P$28_P$28") (pintype "bidirectional"))
      (node (ref "U100") (pin "P$33") (pinfunction "P$33_P$33") (pintype "bidirectional"))
      (node (ref "U100") (pin "P$41") (pinfunction "P$41_P$41") (pintype "bidirectional"))
      (node (ref "U100") (pin "P$47") (pinfunction "P$47_P$47") (pintype "bidirectional"))
      (node (ref "U100") (pin "P$8") (pinfunction "P$8_P$8") (pintype "bidirectional"))
      (node (ref "U11") (pin "13") (pinfunction "EPAD_13") (pintype "passive"))
      (node (ref "U11") (pin "6") (pinfunction "GND_6") (pintype "passive"))
      (node (ref "U12") (pin "13") (pinfunction "EPAD_13") (pintype "passive"))
      (node (ref "U12") (pin "6") (pinfunction "GND_6") (pintype "passive"))
      (node (ref "U2") (pin "15") (pinfunction "DVSS1_15") (pintype "power_in"))
      (node (ref "U2") (pin "72") (pinfunction "DVSS2_72") (pintype "power_in"))
      (node (ref "U2") (pin "82") (pinfunction "DVSS3_82") (pintype "power_in"))
      (node (ref "U4") (pin "13") (pinfunction "EPAD_13") (pintype "passive"))
      (node (ref "U4") (pin "6") (pinfunction "GND_6") (pintype "passive"))
      (node (ref "U5") (pin "13") (pinfunction "EPAD_13") (pintype "passive"))
      (node (ref "U5") (pin "6") (pinfunction "GND_6") (pintype "passive"))
      (node (ref "U6") (pin "VSS") (pinfunction "GND_VSS") (pintype "bidirectional"))
      (node (ref "V_MOT1") (pin "1") (pinfunction "1_1") (pintype "passive"))
      (node (ref "V_MOT2") (pin "1") (pinfunction "1_1") (pintype "passive"))
    )
    (net (code "74") (name "LED0") (class "Default")
      (node (ref "LED2") (pin "A") (pinfunction "A_A") (pintype "passive"))
      (node (ref "U2") (pin "100") (pinfunction "P10.0/UCB3STE_100") (pintype "power_in"))
    )
    (net (code "75") (name "LED1") (class "Default")
      (node (ref "LED1") (pin "A") (pinfunction "A_A") (pintype "passive"))
      (node (ref "U2") (pin "1") (pinfunction "P10.1/UCB3CLK_1") (pintype "power_in"))
    )
    (net (code "76") (name "M1IN1") (class "Default")
      (node (ref "U11") (pin "10") (pinfunction "AIN1_/_APHASE_10") (pintype "input"))
      (node (ref "U2") (pin "52") (pinfunction "P9.0/A17_52") (pintype "power_in"))
    )
    (net (code "77") (name "M1IN2") (class "Default")
      (node (ref "U11") (pin "9") (pinfunction "AIN2_/_AENBL_9") (pintype "input"))
      (node (ref "U2") (pin "53") (pinfunction "P9.1/A16_53") (pintype "power_in"))
    )
    (net (code "78") (name "M2IN1") (class "Default")
      (node (ref "U11") (pin "8") (pinfunction "BIN1_/_BPHASE_8") (pintype "input"))
      (node (ref "U2") (pin "54") (pinfunction "P6.0/A15_54") (pintype "power_in"))
    )
    (net (code "79") (name "M2IN2") (class "Default")
      (node (ref "U11") (pin "7") (pinfunction "BIN2_/_BENBL_7") (pintype "input"))
      (node (ref "U2") (pin "55") (pinfunction "P6.1/A14_55") (pintype "power_in"))
    )
    (net (code "80") (name "M3IN1") (class "Default")
      (node (ref "U12") (pin "10") (pinfunction "AIN1_/_APHASE_10") (pintype "input"))
      (node (ref "U2") (pin "56") (pinfunction "P4.0/A13_56") (pintype "power_in"))
    )
    (net (code "81") (name "M3IN2") (class "Default")
      (node (ref "U12") (pin "9") (pinfunction "AIN2_/_AENBL_9") (pintype "input"))
      (node (ref "U2") (pin "57") (pinfunction "P4.1/A12_57") (pintype "power_in"))
    )
    (net (code "82") (name "M4IN1") (class "Default")
      (node (ref "U12") (pin "8") (pinfunction "BIN1_/_BPHASE_8") (pintype "input"))
      (node (ref "U2") (pin "58") (pinfunction "P4.2/ACLK/TA2CLK/A11_58") (pintype "power_in"))
    )
    (net (code "83") (name "M4IN2") (class "Default")
      (node (ref "U12") (pin "7") (pinfunction "BIN2_/_BENBL_7") (pintype "input"))
      (node (ref "U2") (pin "59") (pinfunction "P4.3/MCLK/RTCCLK/A10_59") (pintype "power_in"))
    )
    (net (code "84") (name "M5IN1") (class "Default")
      (node (ref "U2") (pin "27") (pinfunction "P7.5/PM_TA1.3/C0.4_27") (pintype "power_in"))
      (node (ref "U4") (pin "10") (pinfunction "AIN1_/_APHASE_10") (pintype "input"))
    )
    (net (code "85") (name "M5IN2") (class "Default")
      (node (ref "U2") (pin "28") (pinfunction "P7.6/PM_TA1.2/C0.3_28") (pintype "power_in"))
      (node (ref "U4") (pin "9") (pinfunction "AIN2_/_AENBL_9") (pintype "input"))
    )
    (net (code "86") (name "M6IN1") (class "Default")
      (node (ref "U2") (pin "29") (pinfunction "P7.7/PM_TA1.1/C0.2_29") (pintype "power_in"))
      (node (ref "U4") (pin "8") (pinfunction "BIN1_/_BPHASE_8") (pintype "input"))
    )
    (net (code "87") (name "M6IN2") (class "Default")
      (node (ref "U2") (pin "32") (pinfunction "P3.0/PM_UCA2STE_32") (pintype "power_in"))
      (node (ref "U4") (pin "7") (pinfunction "BIN2_/_BENBL_7") (pintype "input"))
    )
    (net (code "88") (name "M7IN1") (class "Default")
      (node (ref "U2") (pin "36") (pinfunction "P3.4/PM_UCB2STE_36") (pintype "power_in"))
      (node (ref "U5") (pin "10") (pinfunction "AIN1_/_APHASE_10") (pintype "input"))
    )
    (net (code "89") (name "M7IN2") (class "Default")
      (node (ref "U2") (pin "37") (pinfunction "P3.5/PM_UCB2CLK_37") (pintype "power_in"))
      (node (ref "U5") (pin "9") (pinfunction "AIN2_/_AENBL_9") (pintype "input"))
    )
    (net (code "90") (name "M8IN1") (class "Default")
      (node (ref "U2") (pin "38") (pinfunction "P3.6/PM_UCB2SIMO/PM_UCB2SDA_38") (pintype "power_in"))
      (node (ref "U5") (pin "8") (pinfunction "BIN1_/_BPHASE_8") (pintype "input"))
    )
    (net (code "91") (name "M8IN2") (class "Default")
      (node (ref "U2") (pin "39") (pinfunction "P3.7/PM_UCB2SOMI/PM_UCB2SCL_39") (pintype "power_in"))
      (node (ref "U5") (pin "7") (pinfunction "BIN2_/_BENBL_7") (pintype "input"))
    )
    (net (code "92") (name "M1234SLEEP") (class "Default")
      (node (ref "U11") (pin "11") (pinfunction "MODE_11") (pintype "input"))
      (node (ref "U11") (pin "12") (pinfunction "NSLEEP_12") (pintype "input"))
      (node (ref "U12") (pin "11") (pinfunction "MODE_11") (pintype "input"))
      (node (ref "U12") (pin "12") (pinfunction "NSLEEP_12") (pintype "input"))
      (node (ref "U2") (pin "51") (pinfunction "P8.7/A18_51") (pintype "power_in"))
    )
    (net (code "93") (name "M5678SLEEP") (class "Default")
      (node (ref "C21") (pin "1") (pinfunction "1_1") (pintype "passive"))
      (node (ref "C22") (pin "1") (pinfunction "1_1") (pintype "passive"))
      (node (ref "U2") (pin "33") (pinfunction "P3.1/PM_UCA2CLK_33") (pintype "power_in"))
      (node (ref "U4") (pin "12") (pinfunction "NSLEEP_12") (pintype "input"))
      (node (ref "U5") (pin "12") (pinfunction "NSLEEP_12") (pintype "input"))
      (node (ref "VCCMOT") (pin "TP") (pinfunction "TP_TP") (pintype "input"))
    )
    (net (code "94") (name "Net-(3V-PadC)") (class "Default")
      (node (ref "3V") (pin "C") (pinfunction "C_C") (pintype "passive"))
      (node (ref "R102") (pin "2") (pinfunction "2_2") (pintype "passive"))
    )
    (net (code "95") (name "Net-(868MHZ-ANT)") (class "Default")
      (node (ref "868MHZ") (pin "P") (pinfunction "ANT_P") (pintype "bidirectional"))
      (node (ref "U100") (pin "P$23") (pinfunction "P$23_P$23") (pintype "bidirectional"))
    )
    (net (code "96") (name "Net-(BAT-PadC)") (class "Default")
      (node (ref "BAT") (pin "C") (pinfunction "C_C") (pintype "passive"))
      (node (ref "R101") (pin "2") (pinfunction "2_2") (pintype "passive"))
    )
    (net (code "97") (name "Net-(IC1-CAP)") (class "Default")
      (node (ref "C2") (pin "2") (pinfunction "2_2") (pintype "passive"))
      (node (ref "IC1") (pin "9") (pinfunction "CAP_9") (pintype "bidirectional"))
    )
    (net (code "98") (name "Net-(IC1-XIN32)") (class "Default")
      (node (ref "C6") (pin "1") (pinfunction "1_1") (pintype "passive"))
      (node (ref "IC1") (pin "27") (pinfunction "XIN32_27") (pintype "bidirectional"))
      (node (ref "Q1") (pin "2") (pinfunction "2_2") (pintype "passive"))
    )
    (net (code "99") (name "Net-(IC1-XOUT32)") (class "Default")
      (node (ref "C7") (pin "1") (pinfunction "1_1") (pintype "passive"))
      (node (ref "IC1") (pin "26") (pinfunction "XOUT32_26") (pintype "bidirectional"))
      (node (ref "Q1") (pin "1") (pinfunction "1_1") (pintype "passive"))
    )
    (net (code "100") (name "Net-(LED1-PadC)") (class "Default")
      (node (ref "LED1") (pin "C") (pinfunction "C_C") (pintype "passive"))
      (node (ref "R10") (pin "2") (pinfunction "2_2") (pintype "passive"))
    )
    (net (code "101") (name "Net-(LED2-PadC)") (class "Default")
      (node (ref "LED2") (pin "C") (pinfunction "C_C") (pintype "passive"))
      (node (ref "R11") (pin "2") (pinfunction "2_2") (pintype "passive"))
    )
    (net (code "102") (name "Net-(LED5_J-Pad2)") (class "Default")
      (node (ref "LED5_J") (pin "2") (pinfunction "2_2") (pintype "passive"))
      (node (ref "R101") (pin "1") (pinfunction "1_1") (pintype "passive"))
      (node (ref "R102") (pin "1") (pinfunction "1_1") (pintype "passive"))
    )
    (net (code "103") (name "Net-(M5/M6-Pad1)") (class "Default")
      (node (ref "M5/M6") (pin "1") (pinfunction "1_1") (pintype "passive"))
      (node (ref "RS1") (pin "I2") (pinfunction "I2_I2") (pintype "bidirectional"))
    )
    (net (code "104") (name "Net-(M5/M6-Pad3)") (class "Default")
      (node (ref "M5/M6") (pin "3") (pinfunction "3_3") (pintype "passive"))
      (node (ref "RS2") (pin "I2") (pinfunction "I2_I2") (pintype "bidirectional"))
    )
    (net (code "105") (name "Net-(M7/M8-Pad1)") (class "Default")
      (node (ref "M7/M8") (pin "1") (pinfunction "1_1") (pintype "passive"))
      (node (ref "RS3") (pin "I2") (pinfunction "I2_I2") (pintype "bidirectional"))
    )
    (net (code "106") (name "Net-(M7/M8-Pad3)") (class "Default")
      (node (ref "M7/M8") (pin "3") (pinfunction "3_3") (pintype "passive"))
      (node (ref "RS4") (pin "I2") (pinfunction "I2_I2") (pintype "bidirectional"))
    )
    (net (code "107") (name "Net-(Q2-1)") (class "Default")
      (node (ref "C19") (pin "2") (pinfunction "2_2") (pintype "passive"))
      (node (ref "Q2") (pin "P1") (pinfunction "1_P1") (pintype "bidirectional"))
      (node (ref "U2") (pin "42") (pinfunction "PJ.1/LFXOUT_42") (pintype "power_in"))
    )
    (net (code "108") (name "Net-(Q2-2)") (class "Default")
      (node (ref "C18") (pin "2") (pinfunction "2_2") (pintype "passive"))
      (node (ref "Q2") (pin "P2") (pinfunction "2_P2") (pintype "bidirectional"))
      (node (ref "U2") (pin "41") (pinfunction "PJ.0/LFXIN_41") (pintype "power_in"))
    )
    (net (code "109") (name "Net-(T1-D)") (class "Default")
      (node (ref "R8") (pin "1") (pinfunction "1_1") (pintype "passive"))
      (node (ref "T1") (pin "1") (pinfunction "D_1") (pintype "passive"))
      (node (ref "T2") (pin "3") (pinfunction "G_3") (pintype "passive"))
    )
    (net (code "110") (name "Net-(T2-S)") (class "Default")
      (node (ref "5VEXT") (pin "1") (pinfunction "1_1") (pintype "passive"))
      (node (ref "T2") (pin "2") (pinfunction "S_2") (pintype "passive"))
    )
    (net (code "111") (name "Net-(T3-D)") (class "Default")
      (node (ref "DIGITAL_IO1") (pin "9") (pinfunction "9_9") (pintype "passive"))
      (node (ref "T3") (pin "1") (pinfunction "D_1") (pintype "passive"))
    )
    (net (code "112") (name "Net-(T4-D)") (class "Default")
      (node (ref "DIGITAL_IO1") (pin "10") (pinfunction "10_10") (pintype "passive"))
      (node (ref "T4") (pin "1") (pinfunction "D_1") (pintype "passive"))
    )
    (net (code "113") (name "Net-(U1-L)") (class "Default")
      (node (ref "L1") (pin "2") (pinfunction "2_2") (pintype "passive"))
      (node (ref "U1") (pin "3") (pinfunction "L_3") (pintype "input"))
    )
    (net (code "114") (name "Net-(U1-UVLO)") (class "Default")
      (node (ref "R6") (pin "1") (pinfunction "1_1") (pintype "passive"))
      (node (ref "R7") (pin "2") (pinfunction "2_2") (pintype "passive"))
      (node (ref "U1") (pin "7") (pinfunction "UVLO_7") (pintype "input"))
    )
    (net (code "115") (name "Net-(U1-VAUX)") (class "Default")
      (node (ref "C8") (pin "1") (pinfunction "1_1") (pintype "passive"))
      (node (ref "U1") (pin "1") (pinfunction "VAUX_1") (pintype "bidirectional"))
    )
    (net (code "116") (name "Net-(U2-DCOR)") (class "Default")
      (node (ref "R14") (pin "1") (pinfunction "1_1") (pintype "passive"))
      (node (ref "U2") (pin "44") (pinfunction "DCOR_44") (pintype "power_in"))
    )
    (net (code "117") (name "Net-(U2-SWCLKTCK)") (class "Default")
      (node (ref "PROG") (pin "5") (pinfunction "5_5") (pintype "passive"))
      (node (ref "U2") (pin "95") (pinfunction "SWCLKTCK_95") (pintype "power_in"))
    )
    (net (code "118") (name "Net-(U2-SWDIOTMS)") (class "Default")
      (node (ref "PROG") (pin "6") (pinfunction "6_6") (pintype "passive"))
      (node (ref "U2") (pin "94") (pinfunction "SWDIOTMS_94") (pintype "power_in"))
    )
    (net (code "119") (name "Net-(U2-VCORE)") (class "Default")
      (node (ref "C14") (pin "2") (pinfunction "2_2") (pintype "passive"))
      (node (ref "C15") (pin "+") (pinfunction "+_+") (pintype "passive"))
      (node (ref "L2") (pin "1") (pinfunction "1_1") (pintype "passive"))
      (node (ref "U2") (pin "12") (pinfunction "VCORE_12") (pintype "power_in"))
    )
    (net (code "120") (name "Net-(U2-VSW)") (class "Default")
      (node (ref "L2") (pin "2") (pinfunction "2_2") (pintype "passive"))
      (node (ref "U2") (pin "14") (pinfunction "VSW_14") (pintype "power_in"))
    )
    (net (code "121") (name "Net-(U4-AOUT2)") (class "Default")
      (node (ref "M5/M6") (pin "2") (pinfunction "2_2") (pintype "passive"))
      (node (ref "U4") (pin "3") (pinfunction "AOUT2_3") (pintype "output"))
    )
    (net (code "122") (name "Net-(U4-BOUT1)") (class "Default")
      (node (ref "RS2") (pin "I1") (pinfunction "I1_I1") (pintype "bidirectional"))
      (node (ref "U4") (pin "4") (pinfunction "BOUT1_4") (pintype "output"))
    )
    (net (code "123") (name "Net-(U4-BOUT2)") (class "Default")
      (node (ref "M5/M6") (pin "4") (pinfunction "4_4") (pintype "passive"))
      (node (ref "U4") (pin "5") (pinfunction "BOUT2_5") (pintype "output"))
    )
    (net (code "124") (name "Net-(U4-MODE)") (class "Default")
      (node (ref "MOD.") (pin "TP") (pinfunction "TP_TP") (pintype "input"))
      (node (ref "U4") (pin "11") (pinfunction "MODE_11") (pintype "input"))
    )
    (net (code "125") (name "Net-(U5-AOUT1)") (class "Default")
      (node (ref "RS3") (pin "I1") (pinfunction "I1_I1") (pintype "bidirectional"))
      (node (ref "U5") (pin "2") (pinfunction "AOUT1_2") (pintype "output"))
    )
    (net (code "126") (name "Net-(U5-AOUT2)") (class "Default")
      (node (ref "M7/M8") (pin "2") (pinfunction "2_2") (pintype "passive"))
      (node (ref "U5") (pin "3") (pinfunction "AOUT2_3") (pintype "output"))
    )
    (net (code "127") (name "Net-(U5-BOUT1)") (class "Default")
      (node (ref "RS4") (pin "I1") (pinfunction "I1_I1") (pintype "bidirectional"))
      (node (ref "U5") (pin "4") (pinfunction "BOUT1_4") (pintype "output"))
    )
    (net (code "128") (name "Net-(U5-BOUT2)") (class "Default")
      (node (ref "M7/M8") (pin "4") (pinfunction "4_4") (pintype "passive"))
      (node (ref "U5") (pin "5") (pinfunction "BOUT2_5") (pintype "output"))
    )
    (net (code "129") (name "Net-(U5-MODE)") (class "Default")
      (node (ref "MOD") (pin "TP") (pinfunction "TP_TP") (pintype "input"))
      (node (ref "U5") (pin "11") (pinfunction "MODE_11") (pintype "input"))
    )
    (net (code "130") (name "Net-(U7-IN+)") (class "Default")
      (node (ref "RS1") (pin "V1") (pinfunction "V1_V1") (pintype "bidirectional"))
      (node (ref "U7") (pin "4") (pinfunction "IN+_4") (pintype "bidirectional"))
    )
    (net (code "131") (name "Net-(U7-IN-)") (class "Default")
      (node (ref "RS1") (pin "V2") (pinfunction "V2_V2") (pintype "bidirectional"))
      (node (ref "U7") (pin "5") (pinfunction "IN-_5") (pintype "bidirectional"))
    )
    (net (code "132") (name "Net-(U8-IN+)") (class "Default")
      (node (ref "RS2") (pin "V1") (pinfunction "V1_V1") (pintype "bidirectional"))
      (node (ref "U8") (pin "4") (pinfunction "IN+_4") (pintype "bidirectional"))
    )
    (net (code "133") (name "Net-(U8-IN-)") (class "Default")
      (node (ref "RS2") (pin "V2") (pinfunction "V2_V2") (pintype "bidirectional"))
      (node (ref "U8") (pin "5") (pinfunction "IN-_5") (pintype "bidirectional"))
    )
    (net (code "134") (name "Net-(U9-IN+)") (class "Default")
      (node (ref "RS3") (pin "V1") (pinfunction "V1_V1") (pintype "bidirectional"))
      (node (ref "U9") (pin "4") (pinfunction "IN+_4") (pintype "bidirectional"))
    )
    (net (code "135") (name "Net-(U9-IN-)") (class "Default")
      (node (ref "RS3") (pin "V2") (pinfunction "V2_V2") (pintype "bidirectional"))
      (node (ref "U9") (pin "5") (pinfunction "IN-_5") (pintype "bidirectional"))
    )
    (net (code "136") (name "Net-(U10-IN+)") (class "Default")
      (node (ref "RS4") (pin "V1") (pinfunction "V1_V1") (pintype "bidirectional"))
      (node (ref "U10") (pin "4") (pinfunction "IN+_4") (pintype "bidirectional"))
    )
    (net (code "137") (name "Net-(U10-IN-)") (class "Default")
      (node (ref "RS4") (pin "V2") (pinfunction "V2_V2") (pintype "bidirectional"))
      (node (ref "U10") (pin "5") (pinfunction "IN-_5") (pintype "bidirectional"))
    )
    (net (code "138") (name "Net-(U11-AOUT1)") (class "Default")
      (node (ref "M1/M2") (pin "1") (pinfunction "1_1") (pintype "passive"))
      (node (ref "U11") (pin "2") (pinfunction "AOUT1_2") (pintype "output"))
    )
    (net (code "139") (name "Net-(U11-AOUT2)") (class "Default")
      (node (ref "M1/M2") (pin "2") (pinfunction "2_2") (pintype "passive"))
      (node (ref "U11") (pin "3") (pinfunction "AOUT2_3") (pintype "output"))
    )
    (net (code "140") (name "Net-(U11-BOUT1)") (class "Default")
      (node (ref "M1/M2") (pin "3") (pinfunction "3_3") (pintype "passive"))
      (node (ref "U11") (pin "4") (pinfunction "BOUT1_4") (pintype "output"))
    )
    (net (code "141") (name "Net-(U11-BOUT2)") (class "Default")
      (node (ref "M1/M2") (pin "4") (pinfunction "4_4") (pintype "passive"))
      (node (ref "U11") (pin "5") (pinfunction "BOUT2_5") (pintype "output"))
    )
    (net (code "142") (name "Net-(U12-AOUT1)") (class "Default")
      (node (ref "M3/M4") (pin "1") (pinfunction "1_1") (pintype "passive"))
      (node (ref "U12") (pin "2") (pinfunction "AOUT1_2") (pintype "output"))
    )
    (net (code "143") (name "Net-(U12-AOUT2)") (class "Default")
      (node (ref "M3/M4") (pin "2") (pinfunction "2_2") (pintype "passive"))
      (node (ref "U12") (pin "3") (pinfunction "AOUT2_3") (pintype "output"))
    )
    (net (code "144") (name "Net-(U12-BOUT1)") (class "Default")
      (node (ref "M3/M4") (pin "3") (pinfunction "3_3") (pintype "passive"))
      (node (ref "U12") (pin "4") (pinfunction "BOUT1_4") (pintype "output"))
    )
    (net (code "145") (name "Net-(U12-BOUT2)") (class "Default")
      (node (ref "M3/M4") (pin "4") (pinfunction "4_4") (pintype "passive"))
      (node (ref "U12") (pin "5") (pinfunction "BOUT2_5") (pintype "output"))
    )
    (net (code "146") (name "P8.0") (class "Default")
      (node (ref "DIGITAL_IO2") (pin "10") (pinfunction "10_10") (pintype "passive"))
      (node (ref "U2") (pin "30") (pinfunction "P8.0/UCB3STE/TA1.0/C0.1_30") (pintype "power_in"))
    )
    (net (code "147") (name "P8.1") (class "Default")
      (node (ref "DIGITAL_IO2") (pin "9") (pinfunction "9_9") (pintype "passive"))
      (node (ref "U2") (pin "31") (pinfunction "P8.1/UCB3CLK/TA2.0/C0.0_31") (pintype "power_in"))
    )
    (net (code "148") (name "PJ.2") (class "Default")
      (node (ref "T4") (pin "3") (pinfunction "G_3") (pintype "passive"))
      (node (ref "U2") (pin "85") (pinfunction "PJ.2/HFXOUT_85") (pintype "power_in"))
    )
    (net (code "149") (name "PJ.3") (class "Default")
      (node (ref "T3") (pin "3") (pinfunction "G_3") (pintype "passive"))
      (node (ref "U2") (pin "86") (pinfunction "PJ.3/HFXIN_86") (pintype "power_in"))
    )
    (net (code "150") (name "RX1") (class "Default")
      (node (ref "RX1/TX1") (pin "3") (pinfunction "3_3") (pintype "passive"))
      (node (ref "U2") (pin "18") (pinfunction "P2.2/PM_UCA1RXD/PM_UCA1SOMI_18") (pintype "power_in"))
    )
    (net (code "151") (name "TX1") (class "Default")
      (node (ref "RX1/TX1") (pin "2") (pinfunction "2_2") (pintype "passive"))
      (node (ref "U2") (pin "19") (pinfunction "P2.3/PM_UCA1TXD/PM_UCA1SIMO_19") (pintype "power_in"))
    )
    (net (code "152") (name "unconnected-(IC1-PIN1-Pad1)") (class "Default")
      (node (ref "IC1") (pin "1") (pinfunction "PIN1_1") (pintype "bidirectional"))
    )
    (net (code "153") (name "unconnected-(IC1-PIN7-Pad7)") (class "Default")
      (node (ref "IC1") (pin "7") (pinfunction "PIN7_7") (pintype "bidirectional"))
    )
    (net (code "154") (name "unconnected-(IC1-PIN8-Pad8)") (class "Default")
      (node (ref "IC1") (pin "8") (pinfunction "PIN8_8") (pintype "bidirectional"))
    )
    (net (code "155") (name "unconnected-(IC1-PIN12-Pad12)") (class "Default")
      (node (ref "IC1") (pin "12") (pinfunction "PIN12_12") (pintype "bidirectional"))
    )
    (net (code "156") (name "unconnected-(IC1-PIN13-Pad13)") (class "Default")
      (node (ref "IC1") (pin "13") (pinfunction "PIN13_13") (pintype "bidirectional"))
    )
    (net (code "157") (name "unconnected-(IC1-PIN21-Pad21)") (class "Default")
      (node (ref "IC1") (pin "21") (pinfunction "PIN21_21") (pintype "bidirectional"))
    )
    (net (code "158") (name "unconnected-(IC1-PIN22-Pad22)") (class "Default")
      (node (ref "IC1") (pin "22") (pinfunction "PIN22_22") (pintype "bidirectional"))
    )
    (net (code "159") (name "unconnected-(IC1-PIN23-Pad23)") (class "Default")
      (node (ref "IC1") (pin "23") (pinfunction "PIN23_23") (pintype "bidirectional"))
    )
    (net (code "160") (name "unconnected-(IC1-PIN24-Pad24)") (class "Default")
      (node (ref "IC1") (pin "24") (pinfunction "PIN24_24") (pintype "bidirectional"))
    )
    (net (code "161") (name "unconnected-(U100-PadP$25)") (class "Default")
      (node (ref "U100") (pin "P$25") (pinfunction "P$25_P$25") (pintype "bidirectional"))
    )
  )
)
